# OOBD-Tiger.net
KiCad netlist of a schematic drawn in EAGLE
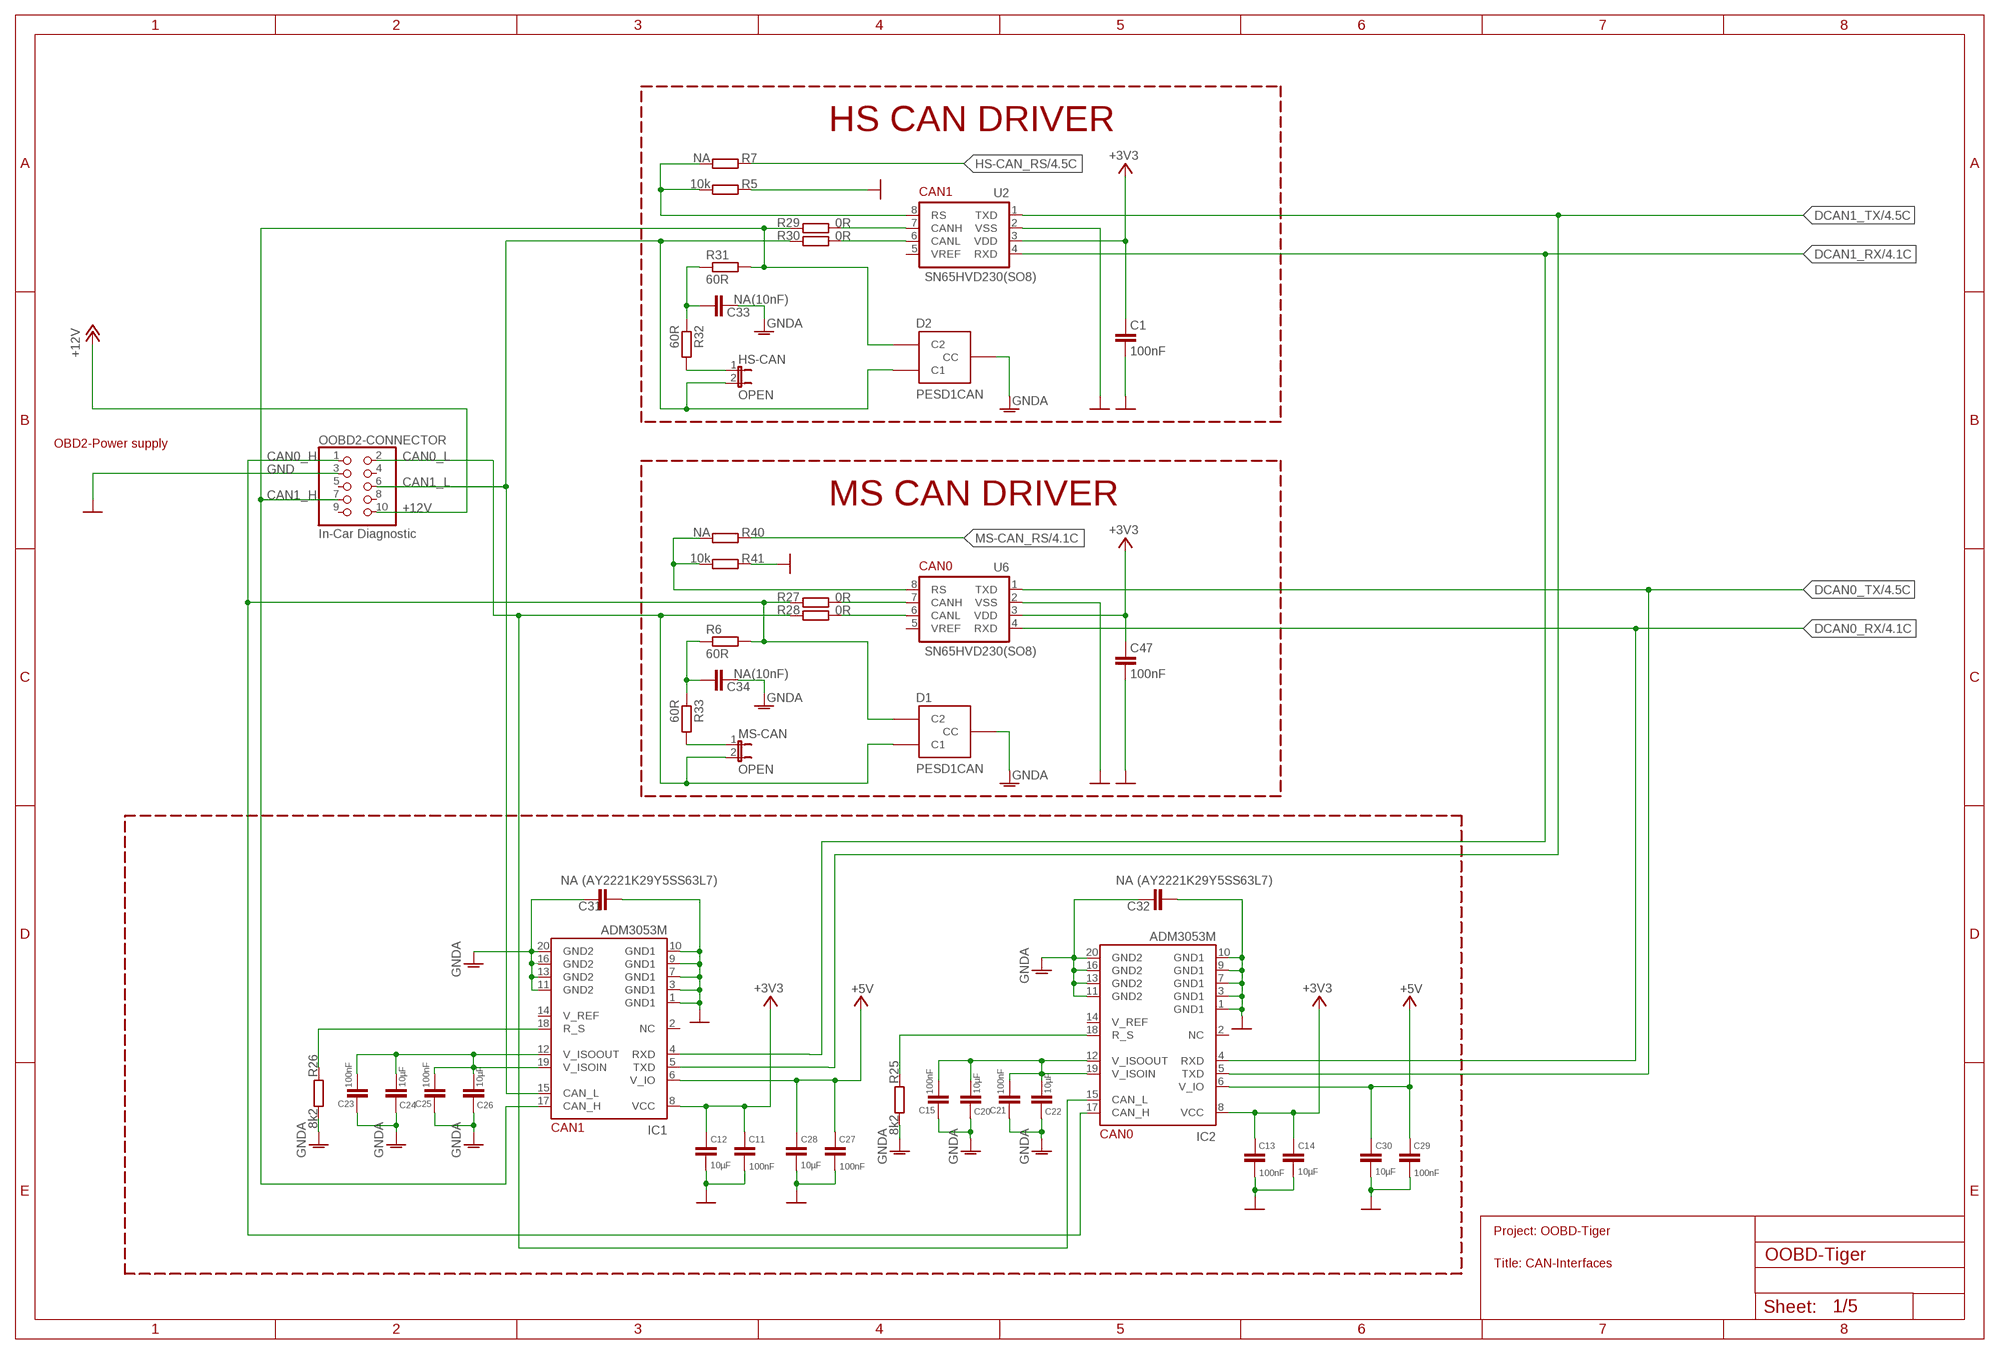
[diagram p0: schematic, sheet 1]
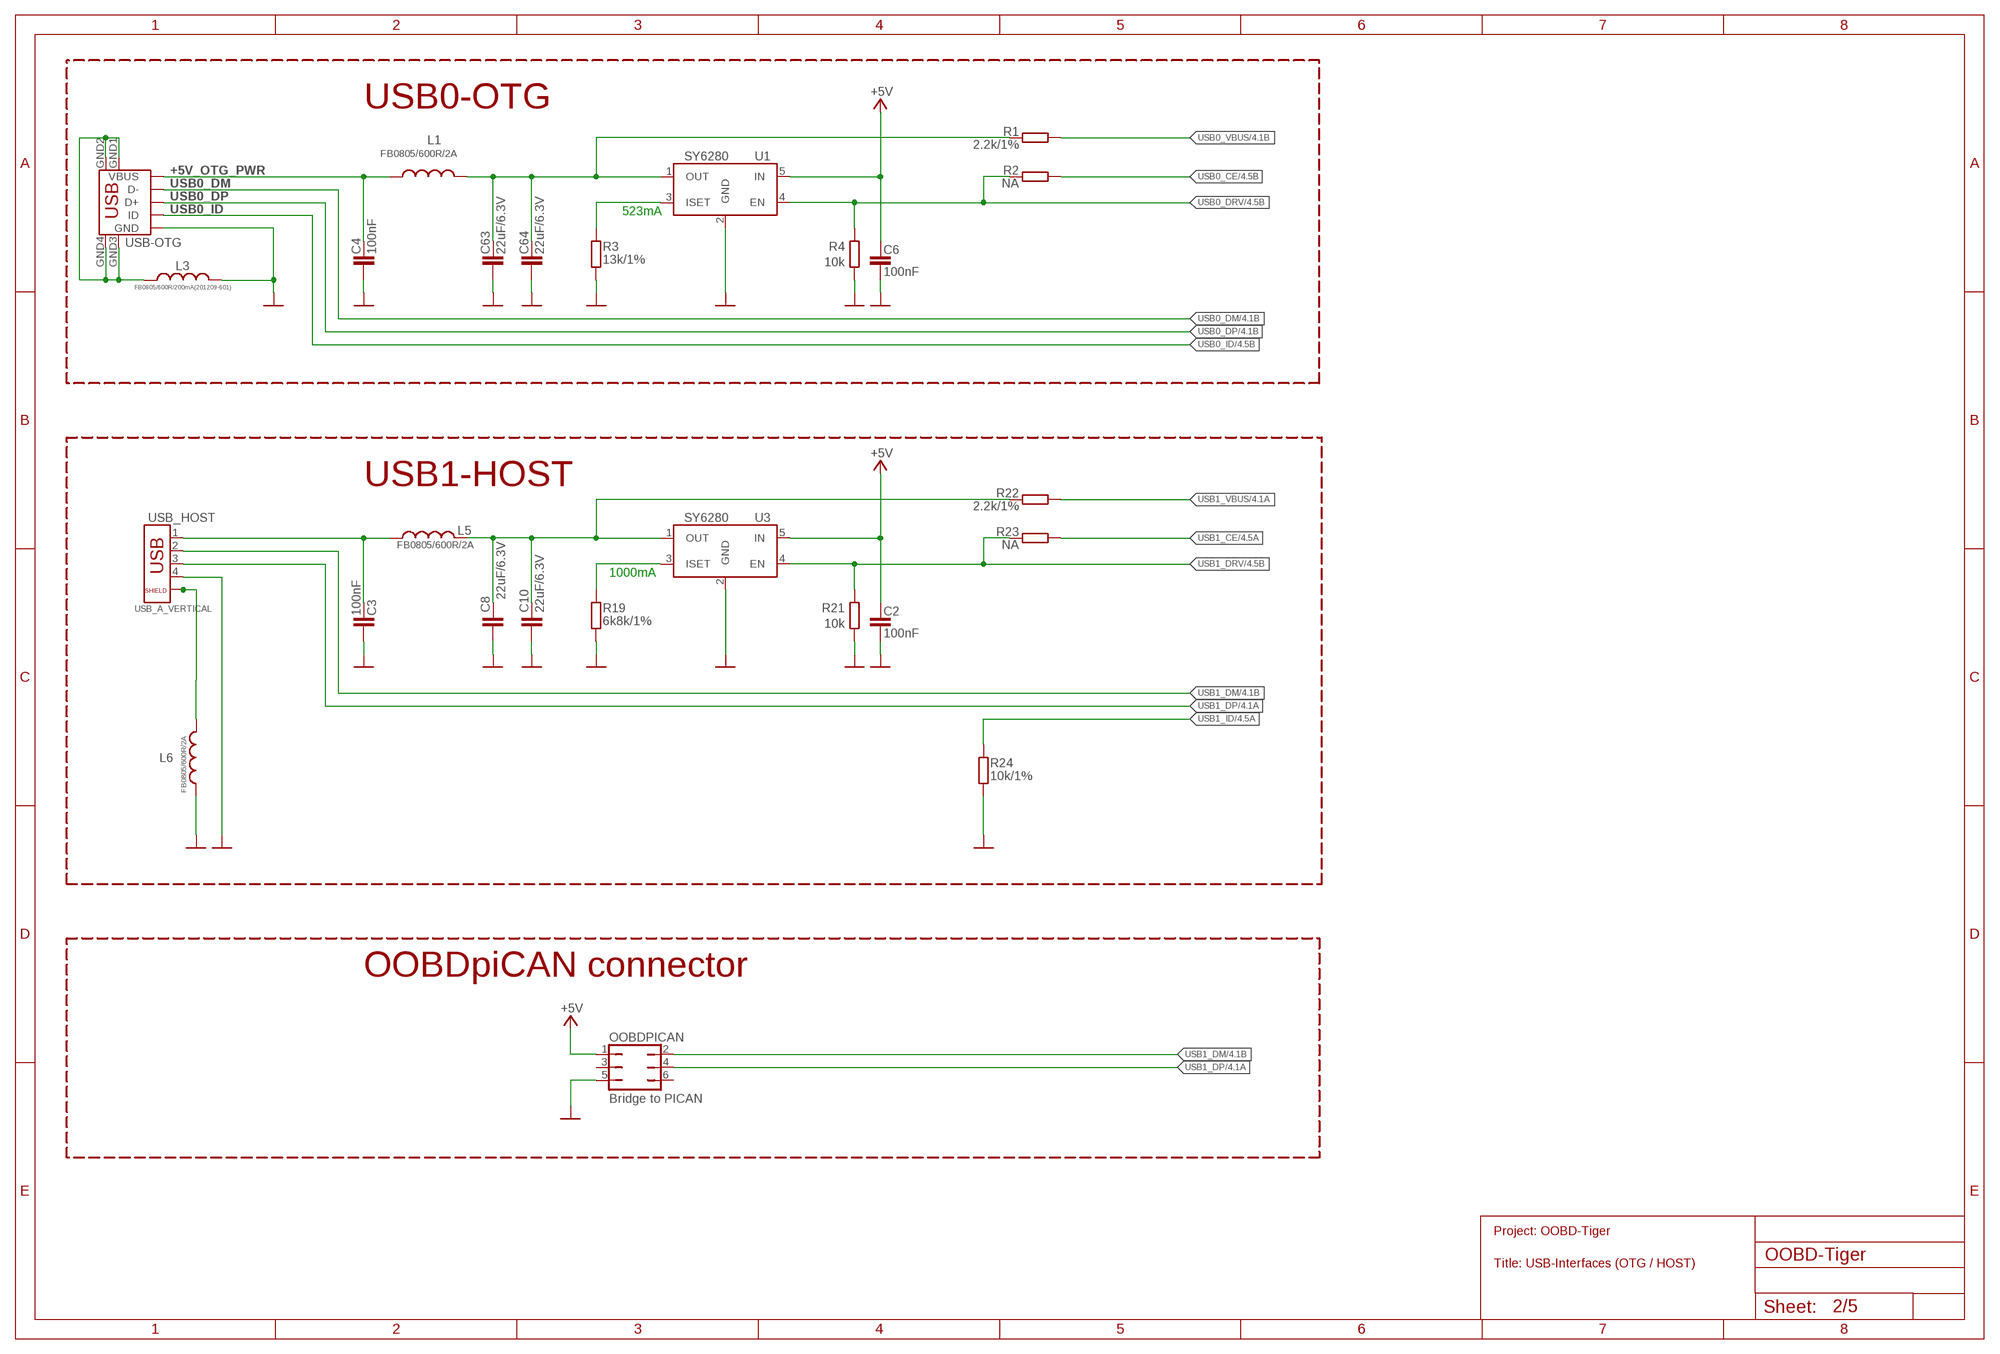
[diagram p1: schematic, sheet 2]
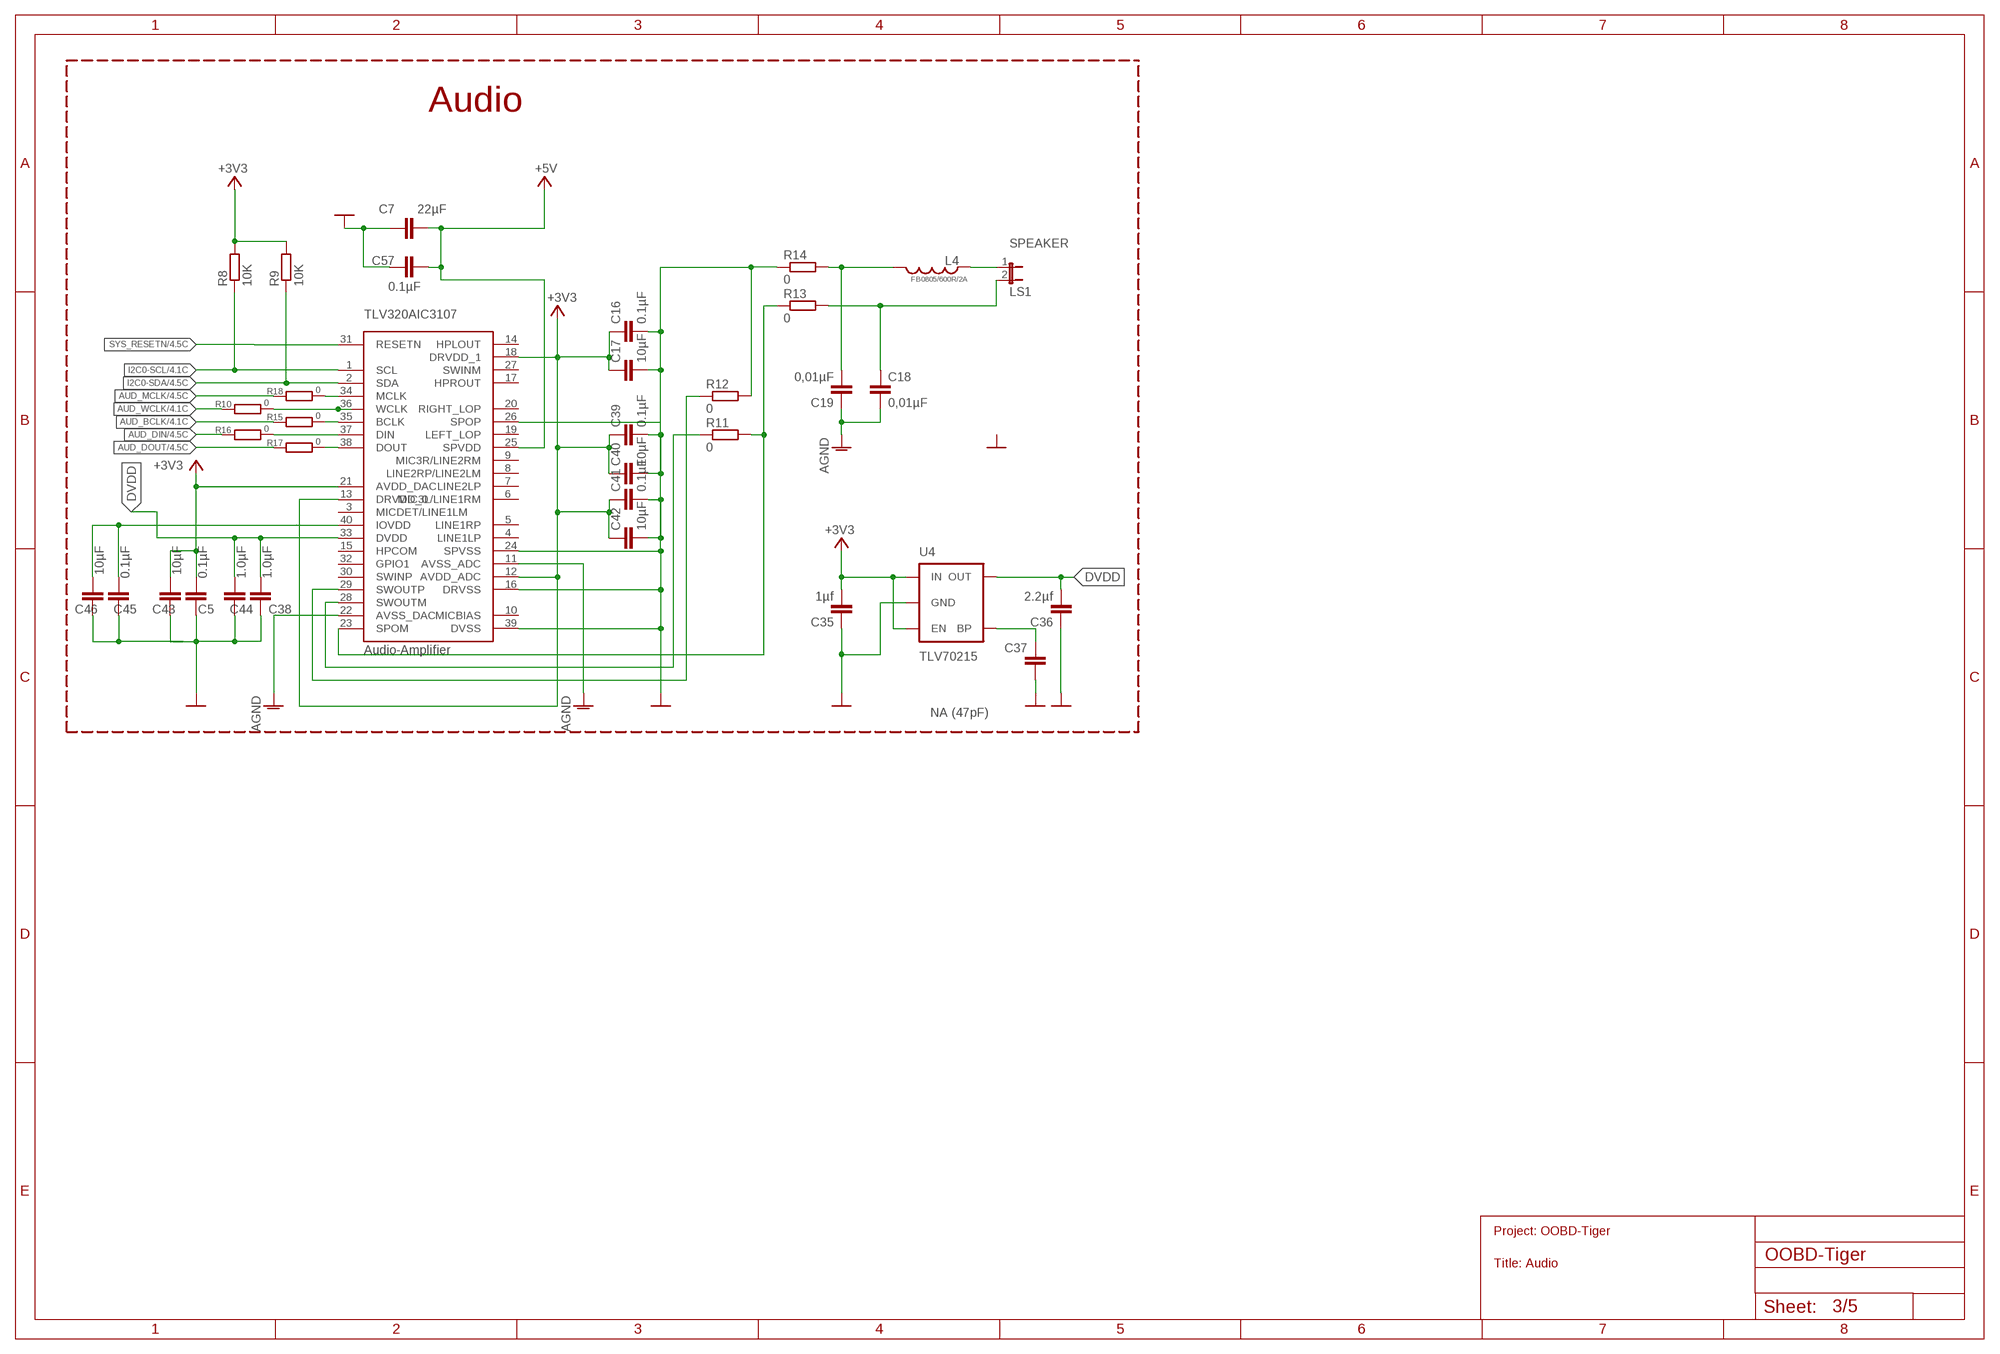
[diagram p2: schematic, sheet 3]
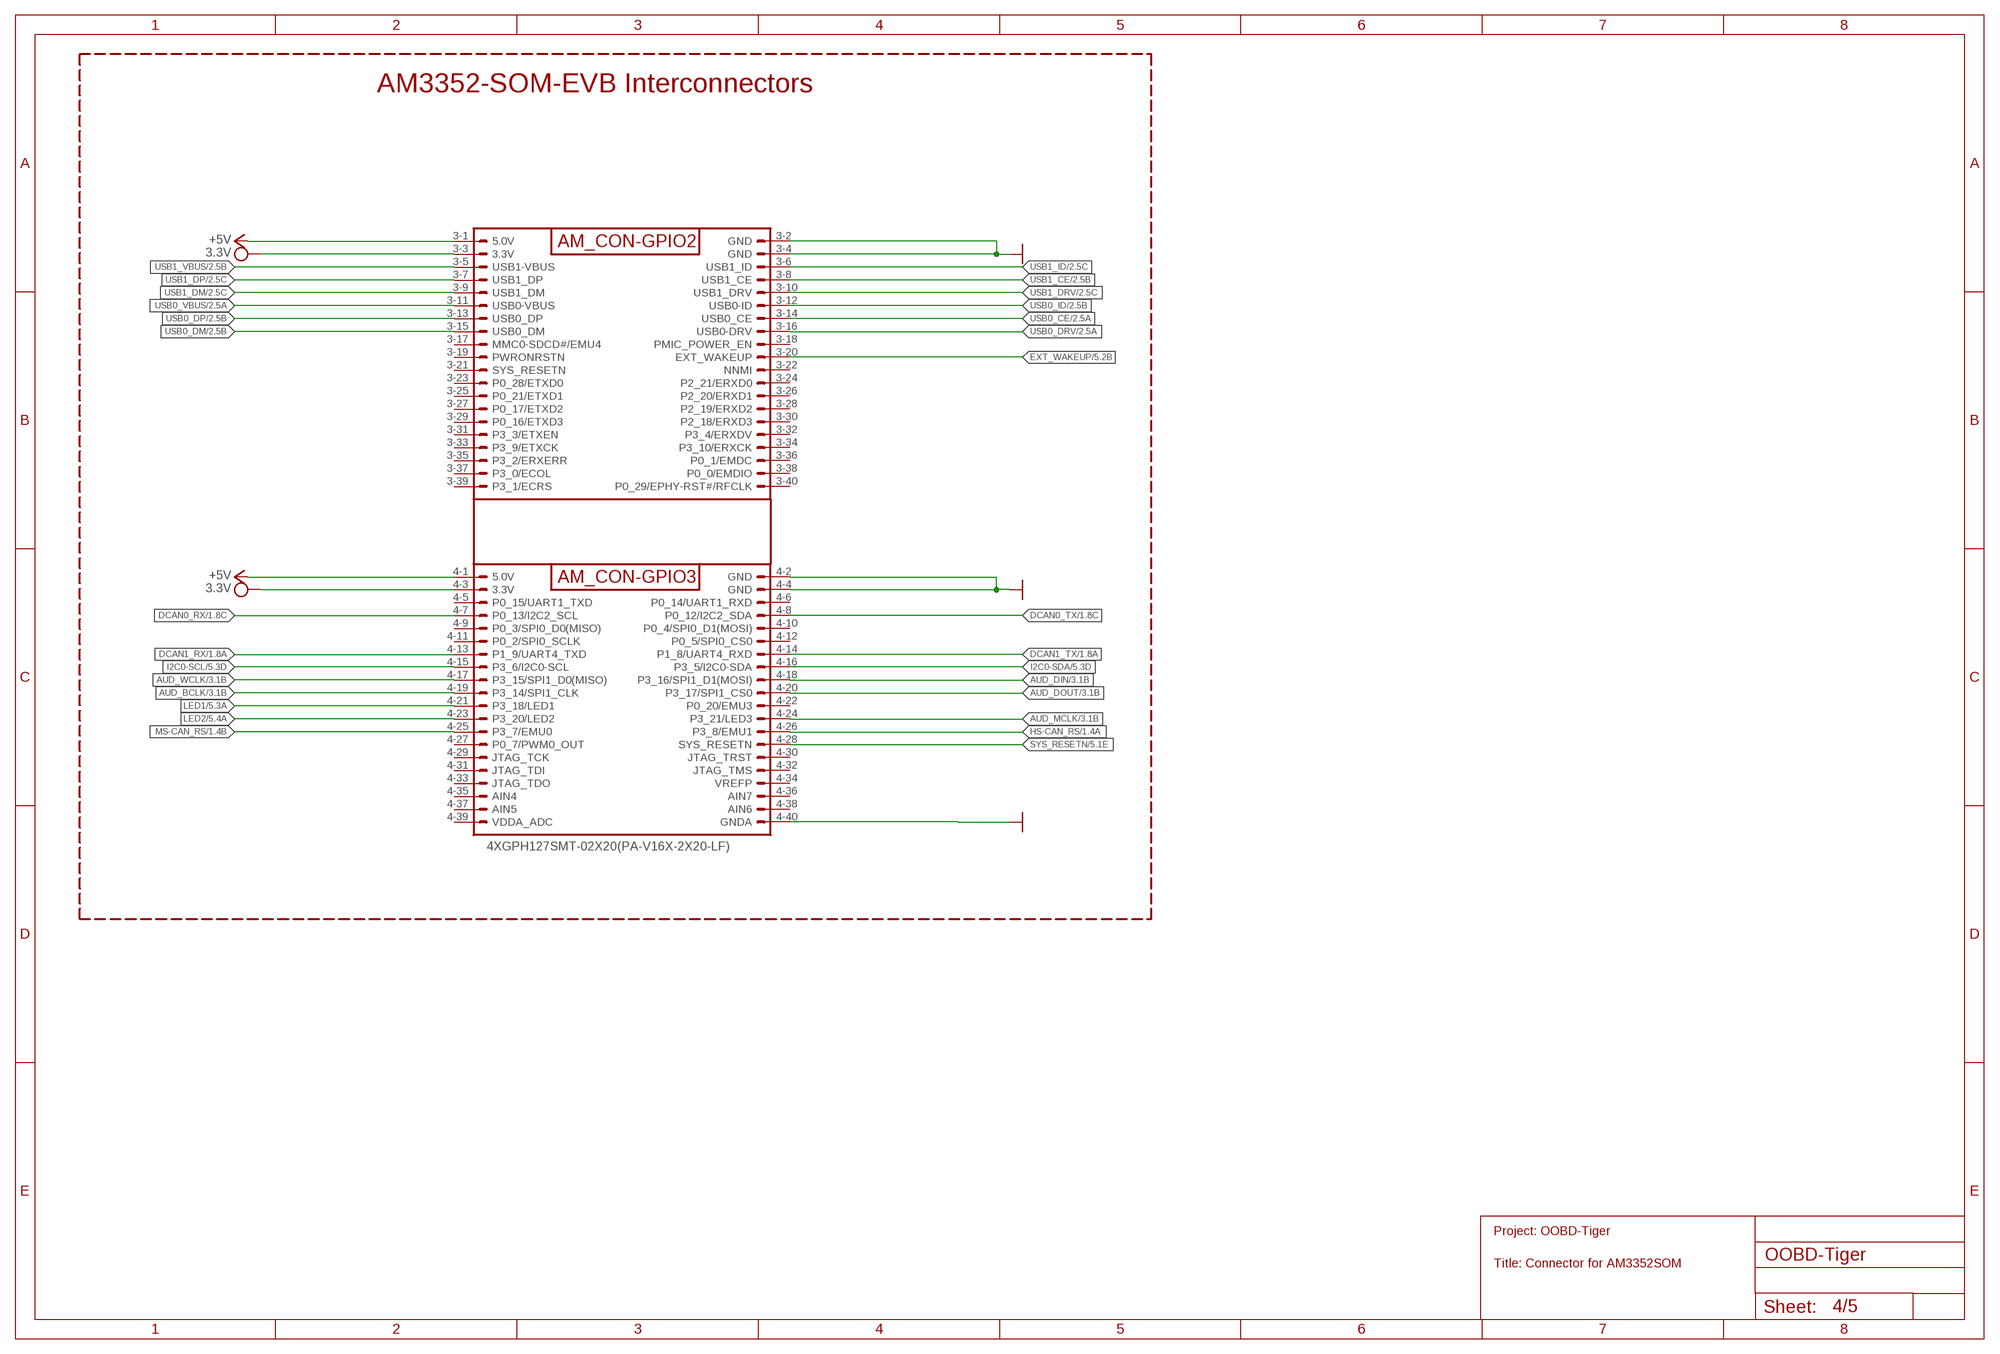
[diagram p3: schematic, sheet 4]
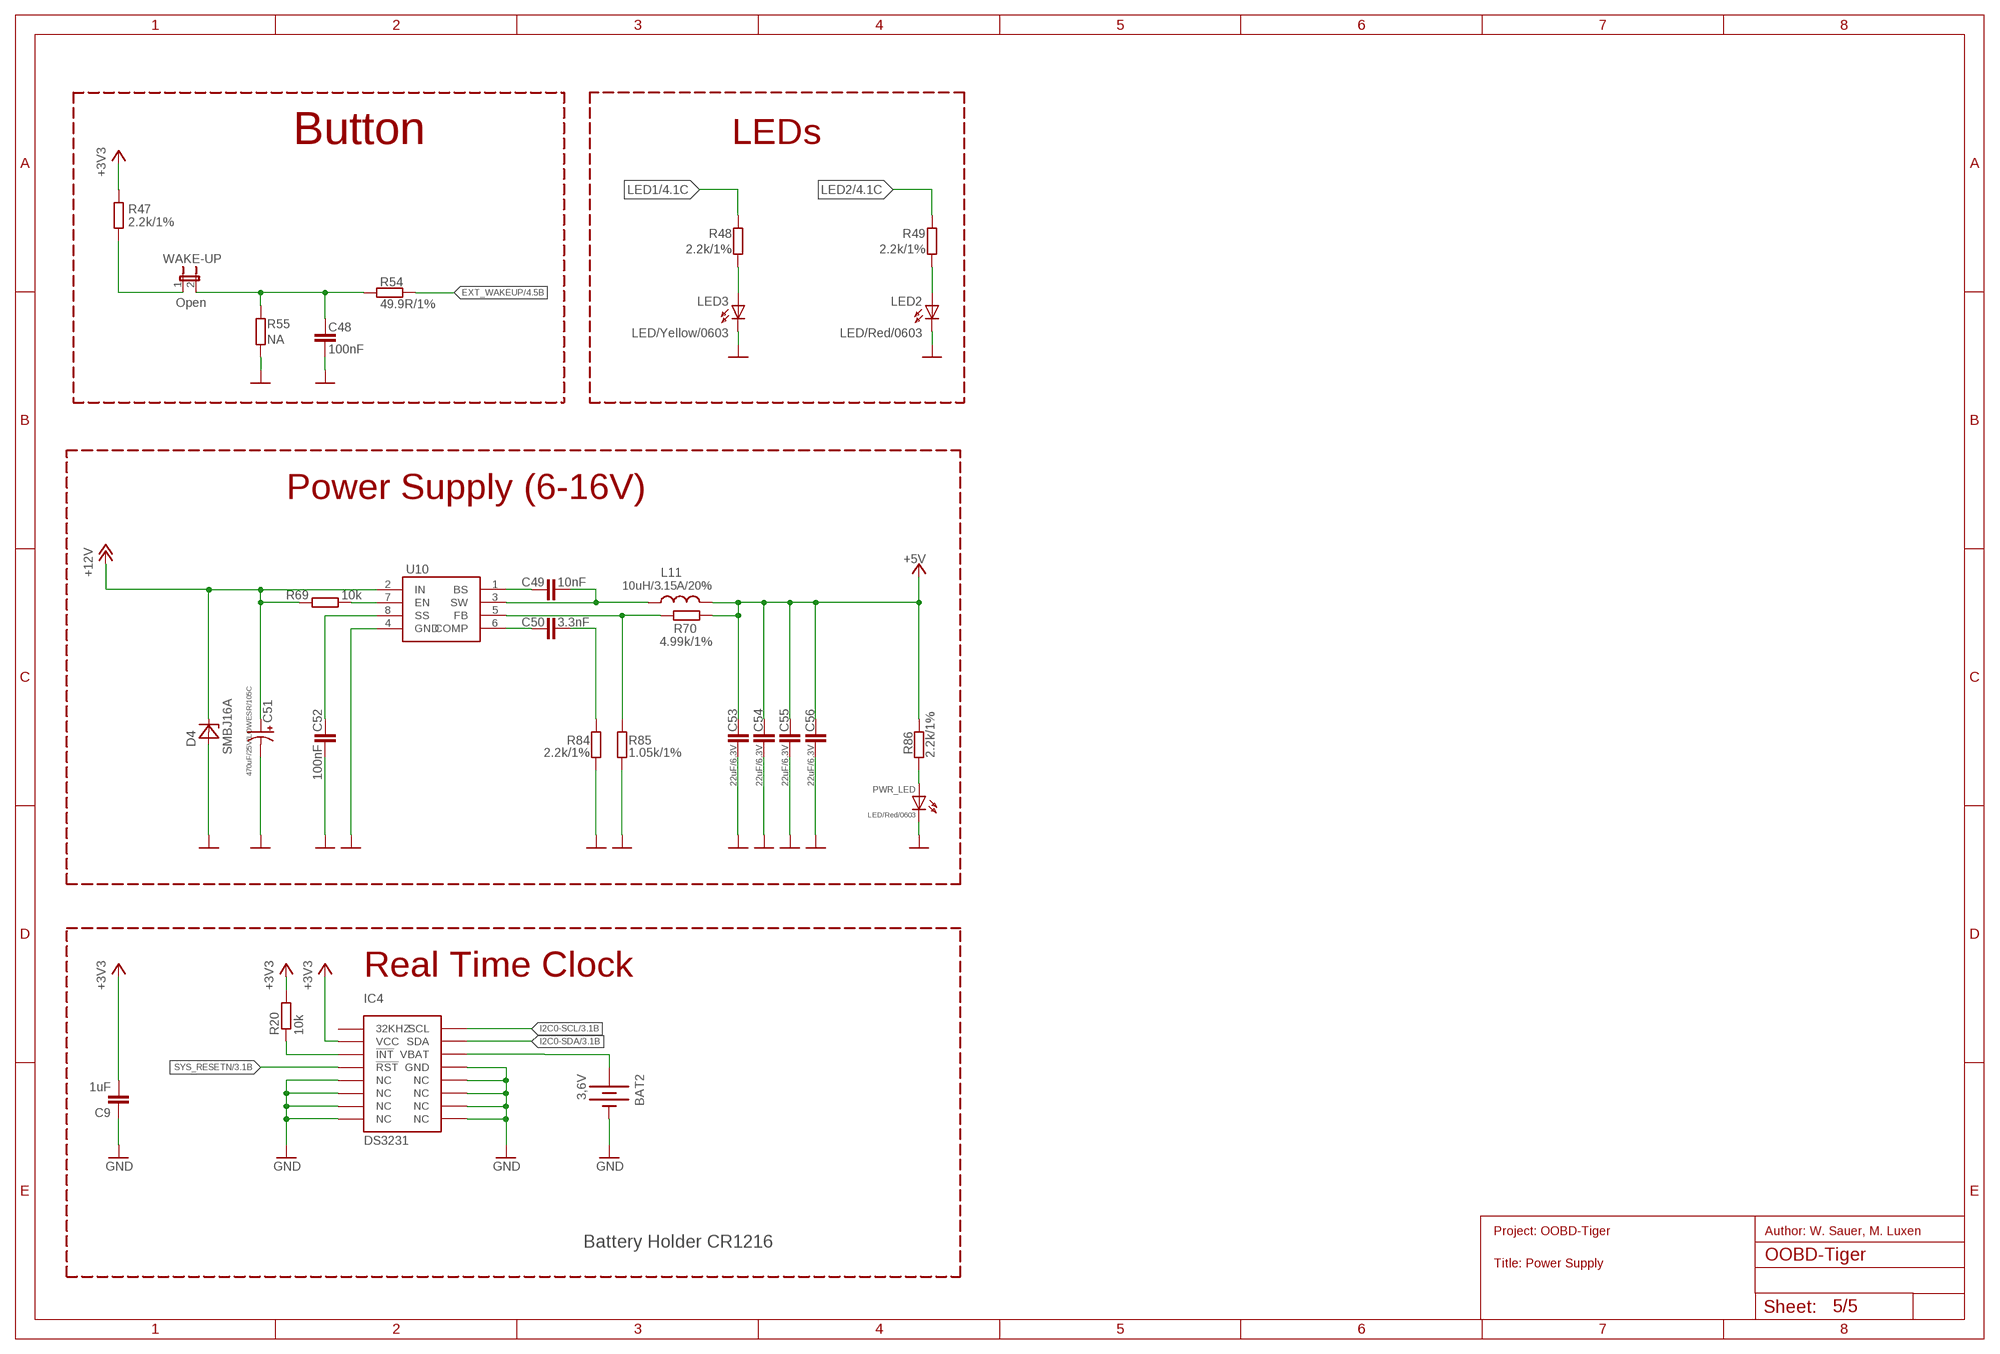
[diagram p4: schematic, sheet 5]

(export (version "E")
  (design (tool "Eeschema 10.0.6"))
  (components
    (comp (ref "C2")
      (value "100nF")
      (footprint "eagle-import:C0603K")
      (libsource (lib "eagle-import") (part "C-EUC0603K"))
    )
    (comp (ref "C3")
      (value "100nF")
      (footprint "eagle-import:C0603K")
      (libsource (lib "eagle-import") (part "C-EUC0603K"))
    )
    (comp (ref "C4")
      (value "100nF")
      (footprint "eagle-import:C0603K")
      (libsource (lib "eagle-import") (part "C-EUC0603K"))
    )
    (comp (ref "C6")
      (value "100nF")
      (footprint "eagle-import:C0603K")
      (libsource (lib "eagle-import") (part "C-EUC0603K"))
    )
    (comp (ref "C8")
      (value "22uF/6.3V")
      (footprint "eagle-import:C0603")
      (libsource (lib "eagle-import") (part "C-EUC0603"))
    )
    (comp (ref "C10")
      (value "22uF/6.3V")
      (footprint "eagle-import:C0603")
      (libsource (lib "eagle-import") (part "C-EUC0603"))
    )
    (comp (ref "C63")
      (value "22uF/6.3V")
      (footprint "eagle-import:C0603")
      (libsource (lib "eagle-import") (part "C-EUC0603"))
    )
    (comp (ref "C64")
      (value "22uF/6.3V")
      (footprint "eagle-import:C0603")
      (libsource (lib "eagle-import") (part "C-EUC0603"))
    )
    (comp (ref "L1")
      (value "FB0805/600R/2A")
      (footprint "eagle-import:L0603")
      (libsource (lib "eagle-import") (part "L-USL0603"))
    )
    (comp (ref "L3")
      (value "FB0805/600R/200mA(201209-601)")
      (footprint "eagle-import:L0603")
      (libsource (lib "eagle-import") (part "L-USL0603"))
    )
    (comp (ref "L5")
      (value "FB0805/600R/2A")
      (footprint "eagle-import:L0603")
      (libsource (lib "eagle-import") (part "L-USL0603"))
    )
    (comp (ref "L6")
      (value "FB0805/600R/2A")
      (footprint "eagle-import:L0603")
      (libsource (lib "eagle-import") (part "L-USL0603"))
    )
    (comp (ref "OOBDPICAN")
      (value "Bridge to PICAN")
      (footprint "eagle-import:JP3Q")
      (libsource (lib "eagle-import") (part "JP3Q"))
    )
    (comp (ref "R1")
      (value "2.2k/1%")
      (footprint "eagle-import:R0603")
      (libsource (lib "eagle-import") (part "R-EU_R0603"))
    )
    (comp (ref "R2")
      (value "NA")
      (footprint "eagle-import:R0603")
      (libsource (lib "eagle-import") (part "R-EU_R0603"))
    )
    (comp (ref "R3")
      (value "13k/1%")
      (footprint "eagle-import:R0603")
      (libsource (lib "eagle-import") (part "R-EU_R0603"))
    )
    (comp (ref "R4")
      (value "10k")
      (footprint "eagle-import:R0603")
      (libsource (lib "eagle-import") (part "R-EU_R0603"))
    )
    (comp (ref "R19")
      (value "6k8k/1%")
      (footprint "eagle-import:R0603")
      (libsource (lib "eagle-import") (part "R-EU_R0603"))
    )
    (comp (ref "R21")
      (value "10k")
      (footprint "eagle-import:R0603")
      (libsource (lib "eagle-import") (part "R-EU_R0603"))
    )
    (comp (ref "R22")
      (value "2.2k/1%")
      (footprint "eagle-import:R0603")
      (libsource (lib "eagle-import") (part "R-EU_R0603"))
    )
    (comp (ref "R23")
      (value "NA")
      (footprint "eagle-import:R0603")
      (libsource (lib "eagle-import") (part "R-EU_R0603"))
    )
    (comp (ref "R24")
      (value "10k/1%")
      (footprint "eagle-import:R0603")
      (libsource (lib "eagle-import") (part "R-EU_R0603"))
    )
    (comp (ref "U1")
      (value "SY6280")
      (footprint "eagle-import:SOT23-5")
      (libsource (lib "eagle-import") (part "SY6280"))
    )
    (comp (ref "U3")
      (value "SY6280")
      (footprint "eagle-import:SOT23-5")
      (libsource (lib "eagle-import") (part "SY6280"))
    )
    (comp (ref "USB_HOST")
      (value "USB_A_VERTICAL")
      (footprint "eagle-import:USB_PN87520_DEV_PTH")
      (libsource (lib "eagle-import") (part "USB_SHIELD1"))
    )
    (comp (ref "USB_OTG")
      (value "USB-OTG")
      (footprint "eagle-import:USB_MINI_9PIN")
      (libsource (lib "eagle-import") (part "MINI_USB9"))
    )
    (comp (ref "C5")
      (value "0.1µF")
      (footprint "eagle-import:0603-CAP")
      (libsource (lib "eagle-import") (part "CAP0603-CAP"))
    )
    (comp (ref "C7")
      (value "22µF")
      (footprint "eagle-import:0603-CAP")
      (libsource (lib "eagle-import") (part "CAP0603-CAP"))
    )
    (comp (ref "C16")
      (value "0.1µF")
      (footprint "eagle-import:0603-CAP")
      (libsource (lib "eagle-import") (part "CAP0603-CAP"))
    )
    (comp (ref "C17")
      (value "10µF")
      (footprint "eagle-import:0603-CAP")
      (libsource (lib "eagle-import") (part "CAP0603-CAP"))
    )
    (comp (ref "C18")
      (value "0,01µF")
      (footprint "eagle-import:0603-CAP")
      (libsource (lib "eagle-import") (part "CAP0603-CAP"))
    )
    (comp (ref "C19")
      (value "0,01µF")
      (footprint "eagle-import:0603-CAP")
      (libsource (lib "eagle-import") (part "CAP0603-CAP"))
    )
    (comp (ref "C35")
      (value "1µf")
      (footprint "eagle-import:0603-CAP")
      (libsource (lib "eagle-import") (part "CAP0603-CAP"))
    )
    (comp (ref "C36")
      (value "2.2µf")
      (footprint "eagle-import:0603-CAP")
      (libsource (lib "eagle-import") (part "CAP0603-CAP"))
    )
    (comp (ref "C37")
      (value "NA (47pF)")
      (footprint "eagle-import:0603-CAP")
      (libsource (lib "eagle-import") (part "CAP0603-CAP"))
    )
    (comp (ref "C38")
      (value "1.0µF")
      (footprint "eagle-import:0603-CAP")
      (libsource (lib "eagle-import") (part "CAP0603-CAP"))
    )
    (comp (ref "C39")
      (value "0.1µF")
      (footprint "eagle-import:0603-CAP")
      (libsource (lib "eagle-import") (part "CAP0603-CAP"))
    )
    (comp (ref "C40")
      (value "10µF")
      (footprint "eagle-import:0603-CAP")
      (libsource (lib "eagle-import") (part "CAP0603-CAP"))
    )
    (comp (ref "C41")
      (value "0.1µF")
      (footprint "eagle-import:0603-CAP")
      (libsource (lib "eagle-import") (part "CAP0603-CAP"))
    )
    (comp (ref "C42")
      (value "10µF")
      (footprint "eagle-import:0603-CAP")
      (libsource (lib "eagle-import") (part "CAP0603-CAP"))
    )
    (comp (ref "C43")
      (value "10µF")
      (footprint "eagle-import:0603-CAP")
      (libsource (lib "eagle-import") (part "CAP0603-CAP"))
    )
    (comp (ref "C44")
      (value "1.0µF")
      (footprint "eagle-import:0603-CAP")
      (libsource (lib "eagle-import") (part "CAP0603-CAP"))
    )
    (comp (ref "C45")
      (value "0.1µF")
      (footprint "eagle-import:0603-CAP")
      (libsource (lib "eagle-import") (part "CAP0603-CAP"))
    )
    (comp (ref "C46")
      (value "10µF")
      (footprint "eagle-import:0603-CAP")
      (libsource (lib "eagle-import") (part "CAP0603-CAP"))
    )
    (comp (ref "C57")
      (value "0.1µF")
      (footprint "eagle-import:0603-CAP")
      (libsource (lib "eagle-import") (part "CAP0603-CAP"))
    )
    (comp (ref "L4")
      (value "FB0805/600R/2A")
      (footprint "eagle-import:L0603")
      (libsource (lib "eagle-import") (part "L-USL0603"))
    )
    (comp (ref "R8")
      (value "10K")
      (footprint "eagle-import:R0603")
      (libsource (lib "eagle-import") (part "resistor_R-EU_R0603"))
    )
    (comp (ref "R9")
      (value "10K")
      (footprint "eagle-import:R0603")
      (libsource (lib "eagle-import") (part "resistor_R-EU_R0603"))
    )
    (comp (ref "R10")
      (value "0")
      (footprint "eagle-import:R0603")
      (libsource (lib "eagle-import") (part "resistor_R-EU_R0603"))
    )
    (comp (ref "R11")
      (value "0")
      (footprint "eagle-import:R0603")
      (libsource (lib "eagle-import") (part "resistor_R-EU_R0603"))
    )
    (comp (ref "R12")
      (value "0")
      (footprint "eagle-import:R0603")
      (libsource (lib "eagle-import") (part "resistor_R-EU_R0603"))
    )
    (comp (ref "R13")
      (value "0")
      (footprint "eagle-import:R0603")
      (libsource (lib "eagle-import") (part "resistor_R-EU_R0603"))
    )
    (comp (ref "R14")
      (value "0")
      (footprint "eagle-import:R0603")
      (libsource (lib "eagle-import") (part "resistor_R-EU_R0603"))
    )
    (comp (ref "R15")
      (value "0")
      (footprint "eagle-import:R0603")
      (libsource (lib "eagle-import") (part "resistor_R-EU_R0603"))
    )
    (comp (ref "R16")
      (value "0")
      (footprint "eagle-import:R0603")
      (libsource (lib "eagle-import") (part "resistor_R-EU_R0603"))
    )
    (comp (ref "R17")
      (value "0")
      (footprint "eagle-import:R0603")
      (libsource (lib "eagle-import") (part "resistor_R-EU_R0603"))
    )
    (comp (ref "R18")
      (value "0")
      (footprint "eagle-import:R0603")
      (libsource (lib "eagle-import") (part "resistor_R-EU_R0603"))
    )
    (comp (ref "SPEAKER")
      (value "LS1")
      (footprint "eagle-import:1X02")
      (libsource (lib "eagle-import") (part "JUMPER-2PTH"))
    )
    (comp (ref "TLV320AIC3107")
      (value "Audio-Amplifier")
      (footprint "eagle-import:QFN40-6X6")
      (libsource (lib "eagle-import") (part "TLV320AIC3107"))
    )
    (comp (ref "U4")
      (value "TLV70215")
      (footprint "eagle-import:SOT23-5")
      (libsource (lib "eagle-import") (part "V_REG_LDOSMD"))
    )
    (comp (ref "C1")
      (value "100nF")
      (footprint "eagle-import:C0603K")
      (libsource (lib "eagle-import") (part "C-EUC0603K"))
    )
    (comp (ref "C11")
      (value "100nF")
      (footprint "eagle-import:C0603K")
      (libsource (lib "eagle-import") (part "C-EUC0603K"))
    )
    (comp (ref "C12")
      (value "10µF")
      (footprint "eagle-import:C0805K")
      (libsource (lib "eagle-import") (part "C-EUC0805K"))
    )
    (comp (ref "C13")
      (value "100nF")
      (footprint "eagle-import:C0603K")
      (libsource (lib "eagle-import") (part "C-EUC0603K"))
    )
    (comp (ref "C14")
      (value "10µF")
      (footprint "eagle-import:C0805K")
      (libsource (lib "eagle-import") (part "C-EUC0805K"))
    )
    (comp (ref "C15")
      (value "100nF")
      (footprint "eagle-import:C0603K")
      (libsource (lib "eagle-import") (part "C-EUC0603K"))
    )
    (comp (ref "C20")
      (value "10µF")
      (footprint "eagle-import:C0805K")
      (libsource (lib "eagle-import") (part "C-EUC0805K"))
    )
    (comp (ref "C21")
      (value "100nF")
      (footprint "eagle-import:C0603K")
      (libsource (lib "eagle-import") (part "C-EUC0603K"))
    )
    (comp (ref "C22")
      (value "10µF")
      (footprint "eagle-import:C0805K")
      (libsource (lib "eagle-import") (part "C-EUC0805K"))
    )
    (comp (ref "C23")
      (value "100nF")
      (footprint "eagle-import:C0603K")
      (libsource (lib "eagle-import") (part "C-EUC0603K"))
    )
    (comp (ref "C24")
      (value "10µF")
      (footprint "eagle-import:C0805K")
      (libsource (lib "eagle-import") (part "C-EUC0805K"))
    )
    (comp (ref "C25")
      (value "100nF")
      (footprint "eagle-import:C0603K")
      (libsource (lib "eagle-import") (part "C-EUC0603K"))
    )
    (comp (ref "C26")
      (value "10µF")
      (footprint "eagle-import:C0805K")
      (libsource (lib "eagle-import") (part "C-EUC0805K"))
    )
    (comp (ref "C27")
      (value "100nF")
      (footprint "eagle-import:C0603K")
      (libsource (lib "eagle-import") (part "C-EUC0603K"))
    )
    (comp (ref "C28")
      (value "10µF")
      (footprint "eagle-import:C0805K")
      (libsource (lib "eagle-import") (part "C-EUC0805K"))
    )
    (comp (ref "C29")
      (value "100nF")
      (footprint "eagle-import:C0603K")
      (libsource (lib "eagle-import") (part "C-EUC0603K"))
    )
    (comp (ref "C30")
      (value "10µF")
      (footprint "eagle-import:C0805K")
      (libsource (lib "eagle-import") (part "C-EUC0805K"))
    )
    (comp (ref "C31")
      (value "NA (AY2221K29Y5SS63L7)")
      (footprint "eagle-import:C075-032X103")
      (libsource (lib "eagle-import") (part "C-EU075-032X103"))
    )
    (comp (ref "C32")
      (value "NA (AY2221K29Y5SS63L7)")
      (footprint "eagle-import:C075-032X103")
      (libsource (lib "eagle-import") (part "C-EU075-032X103"))
    )
    (comp (ref "C33")
      (value "NA(10nF)")
      (footprint "eagle-import:C0603")
      (libsource (lib "eagle-import") (part "resistor_C-EUC0603"))
    )
    (comp (ref "C34")
      (value "NA(10nF)")
      (footprint "eagle-import:C0603")
      (libsource (lib "eagle-import") (part "resistor_C-EUC0603"))
    )
    (comp (ref "C47")
      (value "100nF")
      (footprint "eagle-import:C0603K")
      (libsource (lib "eagle-import") (part "C-EUC0603K"))
    )
    (comp (ref "D1")
      (value "PESD1CAN")
      (footprint "eagle-import:SOT23")
      (libsource (lib "eagle-import") (part "PESD1CAN"))
    )
    (comp (ref "D2")
      (value "PESD1CAN")
      (footprint "eagle-import:SOT23")
      (libsource (lib "eagle-import") (part "PESD1CAN"))
    )
    (comp (ref "HS-CAN")
      (value "OPEN")
      (footprint "eagle-import:1X02")
      (libsource (lib "eagle-import") (part "JUMPER-2PTH"))
    )
    (comp (ref "IC1")
      (value "ADM3053M")
      (footprint "eagle-import:SO20W")
      (libsource (lib "eagle-import") (part "ADM3053M"))
    )
    (comp (ref "IC2")
      (value "ADM3053M")
      (footprint "eagle-import:SO20W")
      (libsource (lib "eagle-import") (part "ADM3053M"))
    )
    (comp (ref "MS-CAN")
      (value "OPEN")
      (footprint "eagle-import:1X02")
      (libsource (lib "eagle-import") (part "JUMPER-2PTH"))
    )
    (comp (ref "OOBD2-CONNECTOR")
      (value "In-Car Diagnostic")
      (footprint "eagle-import:2X05_90")
      (libsource (lib "eagle-import") (part "PINHD-2X5/90"))
    )
    (comp (ref "R5")
      (value "10k")
      (footprint "eagle-import:R0603")
      (libsource (lib "eagle-import") (part "R-EU_R0603"))
    )
    (comp (ref "R6")
      (value "60R")
      (footprint "eagle-import:R0603")
      (libsource (lib "eagle-import") (part "resistor_R-EU_R0603"))
    )
    (comp (ref "R7")
      (value "NA")
      (footprint "eagle-import:R0603")
      (libsource (lib "eagle-import") (part "R-EU_R0603"))
    )
    (comp (ref "R25")
      (value "8k2")
      (footprint "eagle-import:R0603")
      (libsource (lib "eagle-import") (part "R-EU_R0603"))
    )
    (comp (ref "R26")
      (value "8k2")
      (footprint "eagle-import:R0603")
      (libsource (lib "eagle-import") (part "R-EU_R0603"))
    )
    (comp (ref "R27")
      (value "0R")
      (footprint "eagle-import:0207_10")
      (libsource (lib "eagle-import") (part "R-EU_0207/10"))
    )
    (comp (ref "R28")
      (value "0R")
      (footprint "eagle-import:0207_10")
      (libsource (lib "eagle-import") (part "R-EU_0207/10"))
    )
    (comp (ref "R29")
      (value "0R")
      (footprint "eagle-import:0207_10")
      (libsource (lib "eagle-import") (part "R-EU_0207/10"))
    )
    (comp (ref "R30")
      (value "0R")
      (footprint "eagle-import:0207_10")
      (libsource (lib "eagle-import") (part "R-EU_0207/10"))
    )
    (comp (ref "R31")
      (value "60R")
      (footprint "eagle-import:R0603")
      (libsource (lib "eagle-import") (part "resistor_R-EU_R0603"))
    )
    (comp (ref "R32")
      (value "60R")
      (footprint "eagle-import:R0603")
      (libsource (lib "eagle-import") (part "resistor_R-EU_R0603"))
    )
    (comp (ref "R33")
      (value "60R")
      (footprint "eagle-import:R0603")
      (libsource (lib "eagle-import") (part "resistor_R-EU_R0603"))
    )
    (comp (ref "R40")
      (value "NA")
      (footprint "eagle-import:R0603")
      (libsource (lib "eagle-import") (part "R-EU_R0603"))
    )
    (comp (ref "R41")
      (value "10k")
      (footprint "eagle-import:R0603")
      (libsource (lib "eagle-import") (part "R-EU_R0603"))
    )
    (comp (ref "U2")
      (value "SN65HVD230(SO8)")
      (footprint "eagle-import:SO-08")
      (libsource (lib "eagle-import") (part "MCP2551"))
    )
    (comp (ref "U6")
      (value "SN65HVD230(SO8)")
      (footprint "eagle-import:SO-08")
      (libsource (lib "eagle-import") (part "MCP2551"))
    )
    (comp (ref "AM3352-SOM-EVB-PLATFORM")
      (value "4XGPH127SMT-02X20(PA-V16X-2X20-LF)")
      (footprint "eagle-import:OOBD-TIGER-AM3352-SOM")
      (libsource (lib "eagle-import") (part "OOBD-TIGER-AM3352-SOM---4XGPH127SMT-02X20(PA-V16X-2X20-LF)"))
    )
    (comp (ref "BAT2")
      (value "3,6V")
      (footprint "eagle-import:BATTCON_12MM_PTH")
      (libsource (lib "eagle-import") (part "BATTERY12PTH"))
    )
    (comp (ref "C9")
      (value "1uF")
      (footprint "eagle-import:C0603")
      (libsource (lib "eagle-import") (part "C-EUC0603"))
    )
    (comp (ref "C48")
      (value "100nF")
      (footprint "eagle-import:C0603")
      (libsource (lib "eagle-import") (part "C-EUC0603"))
    )
    (comp (ref "C49")
      (value "10nF")
      (footprint "eagle-import:C0603")
      (libsource (lib "eagle-import") (part "C-EUC0603"))
    )
    (comp (ref "C50")
      (value "3.3nF")
      (footprint "eagle-import:C0603")
      (libsource (lib "eagle-import") (part "C-EUC0603"))
    )
    (comp (ref "C51")
      (value "470uF/25V/LOWESR/105C")
      (footprint "eagle-import:PANASONIC_D")
      (libsource (lib "eagle-import") (part "47UF-50V-20%(ELECT)"))
    )
    (comp (ref "C52")
      (value "100nF")
      (footprint "eagle-import:C0603")
      (libsource (lib "eagle-import") (part "C-EUC0603"))
    )
    (comp (ref "C53")
      (value "22uF/6.3V")
      (footprint "eagle-import:C0603")
      (libsource (lib "eagle-import") (part "C-EUC0603"))
    )
    (comp (ref "C54")
      (value "22uF/6.3V")
      (footprint "eagle-import:C0603")
      (libsource (lib "eagle-import") (part "C-EUC0603"))
    )
    (comp (ref "C55")
      (value "22uF/6.3V")
      (footprint "eagle-import:C0603")
      (libsource (lib "eagle-import") (part "C-EUC0603"))
    )
    (comp (ref "C56")
      (value "22uF/6.3V")
      (footprint "eagle-import:C0603")
      (libsource (lib "eagle-import") (part "C-EUC0603"))
    )
    (comp (ref "D4")
      (value "SMBJ16A")
      (footprint "eagle-import:DO214AA")
      (libsource (lib "eagle-import") (part "SMBJ16A"))
    )
    (comp (ref "IC4")
      (value "DS3231")
      (footprint "eagle-import:SOIC-16W")
      (libsource (lib "eagle-import") (part "DS3231SOIC-16W"))
    )
    (comp (ref "L11")
      (value "10uH/3.15A/20%")
      (footprint "eagle-import:8X8MM_3131")
      (libsource (lib "eagle-import") (part "LLQH88PN100M38"))
    )
    (comp (ref "LED2")
      (value "LED/Red/0603")
      (footprint "eagle-import:LED_0603")
      (libsource (lib "eagle-import") (part "LEDLED_0603"))
    )
    (comp (ref "LED3")
      (value "LED/Yellow/0603")
      (footprint "eagle-import:LED_0603")
      (libsource (lib "eagle-import") (part "LEDLED_0603"))
    )
    (comp (ref "PWR_LED")
      (value "LED/Red/0603")
      (footprint "eagle-import:LED-0603")
      (libsource (lib "eagle-import") (part "LED0603DWS"))
    )
    (comp (ref "R20")
      (value "10k")
      (footprint "eagle-import:R0603")
      (libsource (lib "eagle-import") (part "R-EU_R0603"))
    )
    (comp (ref "R47")
      (value "2.2k/1%")
      (footprint "eagle-import:R0603")
      (libsource (lib "eagle-import") (part "R-EU_R0603"))
    )
    (comp (ref "R48")
      (value "2.2k/1%")
      (footprint "eagle-import:R0603")
      (libsource (lib "eagle-import") (part "R-EU_R0603"))
    )
    (comp (ref "R49")
      (value "2.2k/1%")
      (footprint "eagle-import:R0603")
      (libsource (lib "eagle-import") (part "R-EU_R0603"))
    )
    (comp (ref "R54")
      (value "49.9R/1%")
      (footprint "eagle-import:R0603")
      (libsource (lib "eagle-import") (part "R-EU_R0603"))
    )
    (comp (ref "R55")
      (value "NA")
      (footprint "eagle-import:R0603")
      (libsource (lib "eagle-import") (part "R-EU_R0603"))
    )
    (comp (ref "R69")
      (value "10k")
      (footprint "eagle-import:R0603")
      (libsource (lib "eagle-import") (part "R-EU_R0603"))
    )
    (comp (ref "R70")
      (value "4.99k/1%")
      (footprint "eagle-import:R0603")
      (libsource (lib "eagle-import") (part "R-EU_R0603"))
    )
    (comp (ref "R84")
      (value "2.2k/1%")
      (footprint "eagle-import:R0603")
      (libsource (lib "eagle-import") (part "R-EU_R0603"))
    )
    (comp (ref "R85")
      (value "1.05k/1%")
      (footprint "eagle-import:R0603")
      (libsource (lib "eagle-import") (part "R-EU_R0603"))
    )
    (comp (ref "R86")
      (value "2.2k/1%")
      (footprint "eagle-import:R0603")
      (libsource (lib "eagle-import") (part "R-EU_R0603"))
    )
    (comp (ref "U10")
      (value "MP1482DS")
      (footprint "eagle-import:SOIC8")
      (libsource (lib "eagle-import") (part "MP1482"))
    )
    (comp (ref "WAKE-UP")
      (value "Open")
      (footprint "eagle-import:1X02_LOCK")
      (libsource (lib "eagle-import") (part "JUMPER-2PTH_LOCK"))
    )
  )
  (nets
    (net (code "1") (name "+3V3") (class "Default")
      (node (ref "C1") (pin "1") (pinfunction "1_1") (pintype "passive"))
      (node (ref "C11") (pin "1") (pinfunction "1_1") (pintype "passive"))
      (node (ref "C12") (pin "1") (pinfunction "1_1") (pintype "passive"))
      (node (ref "C13") (pin "1") (pinfunction "1_1") (pintype "passive"))
      (node (ref "C14") (pin "1") (pinfunction "1_1") (pintype "passive"))
      (node (ref "C16") (pin "1") (pinfunction "1_1") (pintype "passive"))
      (node (ref "C17") (pin "1") (pinfunction "1_1") (pintype "passive"))
      (node (ref "C35") (pin "2") (pinfunction "2_2") (pintype "passive"))
      (node (ref "C39") (pin "1") (pinfunction "1_1") (pintype "passive"))
      (node (ref "C40") (pin "1") (pinfunction "1_1") (pintype "passive"))
      (node (ref "C41") (pin "1") (pinfunction "1_1") (pintype "passive"))
      (node (ref "C42") (pin "1") (pinfunction "1_1") (pintype "passive"))
      (node (ref "C43") (pin "2") (pinfunction "2_2") (pintype "passive"))
      (node (ref "C47") (pin "1") (pinfunction "1_1") (pintype "passive"))
      (node (ref "C5") (pin "2") (pinfunction "2_2") (pintype "passive"))
      (node (ref "C9") (pin "2") (pinfunction "2_2") (pintype "passive"))
      (node (ref "IC1") (pin "8") (pinfunction "VCC_8") (pintype "power_in"))
      (node (ref "IC2") (pin "8") (pinfunction "VCC_8") (pintype "power_in"))
      (node (ref "IC4") (pin "2") (pinfunction "VCC_2") (pintype "bidirectional"))
      (node (ref "R20") (pin "2") (pinfunction "2_2") (pintype "passive"))
      (node (ref "R47") (pin "2") (pinfunction "2_2") (pintype "passive"))
      (node (ref "R8") (pin "2") (pinfunction "2_2") (pintype "passive"))
      (node (ref "R9") (pin "2") (pinfunction "2_2") (pintype "passive"))
      (node (ref "TLV320AIC3107") (pin "12") (pinfunction "AVDD_ADC_12") (pintype "bidirectional"))
      (node (ref "TLV320AIC3107") (pin "13") (pinfunction "DRVDD_0_13") (pintype "bidirectional"))
      (node (ref "TLV320AIC3107") (pin "18") (pinfunction "DRVDD_1_18") (pintype "bidirectional"))
      (node (ref "TLV320AIC3107") (pin "21") (pinfunction "AVDD_DAC_21") (pintype "bidirectional"))
      (node (ref "U2") (pin "3") (pinfunction "VDD_3") (pintype "power_in"))
      (node (ref "U4") (pin "1") (pinfunction "IN_1") (pintype "input"))
      (node (ref "U4") (pin "3") (pinfunction "EN_3") (pintype "input"))
      (node (ref "U6") (pin "3") (pinfunction "VDD_3") (pintype "power_in"))
    )
    (net (code "2") (name "+5V") (class "Default")
      (node (ref "AM3352-SOM-EVB-PLATFORM") (pin "3-1") (pinfunction "5.0V_3-1") (pintype "passive"))
      (node (ref "AM3352-SOM-EVB-PLATFORM") (pin "4-1") (pinfunction "5.0V_4-1") (pintype "passive"))
      (node (ref "C2") (pin "1") (pinfunction "1_1") (pintype "passive"))
      (node (ref "C27") (pin "1") (pinfunction "1_1") (pintype "passive"))
      (node (ref "C28") (pin "1") (pinfunction "1_1") (pintype "passive"))
      (node (ref "C29") (pin "1") (pinfunction "1_1") (pintype "passive"))
      (node (ref "C30") (pin "1") (pinfunction "1_1") (pintype "passive"))
      (node (ref "C53") (pin "1") (pinfunction "1_1") (pintype "passive"))
      (node (ref "C54") (pin "1") (pinfunction "1_1") (pintype "passive"))
      (node (ref "C55") (pin "1") (pinfunction "1_1") (pintype "passive"))
      (node (ref "C56") (pin "1") (pinfunction "1_1") (pintype "passive"))
      (node (ref "C57") (pin "2") (pinfunction "2_2") (pintype "passive"))
      (node (ref "C6") (pin "1") (pinfunction "1_1") (pintype "passive"))
      (node (ref "C7") (pin "2") (pinfunction "2_2") (pintype "passive"))
      (node (ref "IC1") (pin "6") (pinfunction "V_IO_6") (pintype "power_in"))
      (node (ref "IC2") (pin "6") (pinfunction "V_IO_6") (pintype "power_in"))
      (node (ref "L11") (pin "2") (pinfunction "2_2") (pintype "passive"))
      (node (ref "OOBDPICAN") (pin "1") (pinfunction "1_1") (pintype "passive"))
      (node (ref "R70") (pin "2") (pinfunction "2_2") (pintype "passive"))
      (node (ref "R86") (pin "1") (pinfunction "1_1") (pintype "passive"))
      (node (ref "TLV320AIC3107") (pin "25") (pinfunction "SPVDD_25") (pintype "bidirectional"))
      (node (ref "U1") (pin "5") (pinfunction "IN_5") (pintype "power_in"))
      (node (ref "U3") (pin "5") (pinfunction "IN_5") (pintype "power_in"))
    )
    (net (code "3") (name "+5V_OTG_PWR") (class "Default")
      (node (ref "C4") (pin "1") (pinfunction "1_1") (pintype "passive"))
      (node (ref "L1") (pin "1") (pinfunction "1_1") (pintype "passive"))
      (node (ref "USB_OTG") (pin "VBUS") (pinfunction "VBUS_VBUS") (pintype "power_in"))
    )
    (net (code "4") (name "+12V") (class "Default")
      (node (ref "C51") (pin "+") (pinfunction "+_+") (pintype "passive"))
      (node (ref "D4") (pin "C") (pinfunction "C_C") (pintype "passive"))
      (node (ref "OOBD2-CONNECTOR") (pin "10") (pinfunction "10_10") (pintype "passive"))
      (node (ref "R69") (pin "1") (pinfunction "1_1") (pintype "passive"))
      (node (ref "U10") (pin "2") (pinfunction "IN_2") (pintype "bidirectional"))
    )
    (net (code "5") (name "3V3") (class "Default")
      (node (ref "AM3352-SOM-EVB-PLATFORM") (pin "3-3") (pinfunction "3.3V_3-3") (pintype "passive"))
      (node (ref "AM3352-SOM-EVB-PLATFORM") (pin "4-3") (pinfunction "3.3V_4-3") (pintype "passive"))
    )
    (net (code "6") (name "AGND") (class "Default")
      (node (ref "C18") (pin "2") (pinfunction "2_2") (pintype "passive"))
      (node (ref "C19") (pin "1") (pinfunction "1_1") (pintype "passive"))
      (node (ref "TLV320AIC3107") (pin "11") (pinfunction "AVSS_ADC_11") (pintype "bidirectional"))
      (node (ref "TLV320AIC3107") (pin "22") (pinfunction "AVSS_DAC_22") (pintype "bidirectional"))
    )
    (net (code "7") (name "AUD_BCLK") (class "Default")
      (node (ref "AM3352-SOM-EVB-PLATFORM") (pin "4-19") (pinfunction "P3_14/SPI1_CLK_4-19") (pintype "passive"))
      (node (ref "R15") (pin "1") (pinfunction "1_1") (pintype "passive"))
    )
    (net (code "8") (name "AUD_DIN") (class "Default")
      (node (ref "AM3352-SOM-EVB-PLATFORM") (pin "4-18") (pinfunction "P3_16/SPI1_D1(MOSI)_4-18") (pintype "passive"))
      (node (ref "R16") (pin "1") (pinfunction "1_1") (pintype "passive"))
    )
    (net (code "9") (name "AUD_DOUT") (class "Default")
      (node (ref "AM3352-SOM-EVB-PLATFORM") (pin "4-20") (pinfunction "P3_17/SPI1_CS0_4-20") (pintype "passive"))
      (node (ref "R17") (pin "1") (pinfunction "1_1") (pintype "passive"))
    )
    (net (code "10") (name "AUD_MCLK") (class "Default")
      (node (ref "AM3352-SOM-EVB-PLATFORM") (pin "4-24") (pinfunction "P3_21/LED3_4-24") (pintype "passive"))
      (node (ref "R18") (pin "1") (pinfunction "1_1") (pintype "passive"))
    )
    (net (code "11") (name "AUD_WCLK") (class "Default")
      (node (ref "AM3352-SOM-EVB-PLATFORM") (pin "4-17") (pinfunction "P3_15/SPI1_D0(MISO)_4-17") (pintype "passive"))
      (node (ref "R10") (pin "1") (pinfunction "1_1") (pintype "passive"))
    )
    (net (code "12") (name "CAN0_H") (class "Default")
      (node (ref "D1") (pin "2") (pinfunction "C2_2") (pintype "bidirectional"))
      (node (ref "IC2") (pin "17") (pinfunction "CAN_H_17") (pintype "bidirectional"))
      (node (ref "OOBD2-CONNECTOR") (pin "1") (pinfunction "1_1") (pintype "passive"))
      (node (ref "R27") (pin "1") (pinfunction "1_1") (pintype "passive"))
      (node (ref "R6") (pin "2") (pinfunction "2_2") (pintype "passive"))
    )
    (net (code "13") (name "CAN0_L") (class "Default")
      (node (ref "D1") (pin "1") (pinfunction "C1_1") (pintype "bidirectional"))
      (node (ref "IC2") (pin "15") (pinfunction "CAN_L_15") (pintype "bidirectional"))
      (node (ref "MS-CAN") (pin "2") (pinfunction "2_2") (pintype "passive"))
      (node (ref "OOBD2-CONNECTOR") (pin "2") (pinfunction "2_2") (pintype "passive"))
      (node (ref "R28") (pin "1") (pinfunction "1_1") (pintype "passive"))
    )
    (net (code "14") (name "CAN1_H") (class "Default")
      (node (ref "D2") (pin "2") (pinfunction "C2_2") (pintype "bidirectional"))
      (node (ref "IC1") (pin "17") (pinfunction "CAN_H_17") (pintype "bidirectional"))
      (node (ref "OOBD2-CONNECTOR") (pin "7") (pinfunction "7_7") (pintype "passive"))
      (node (ref "R29") (pin "2") (pinfunction "2_2") (pintype "passive"))
      (node (ref "R31") (pin "2") (pinfunction "2_2") (pintype "passive"))
    )
    (net (code "15") (name "CAN1_L") (class "Default")
      (node (ref "D2") (pin "1") (pinfunction "C1_1") (pintype "bidirectional"))
      (node (ref "HS-CAN") (pin "2") (pinfunction "2_2") (pintype "passive"))
      (node (ref "IC1") (pin "15") (pinfunction "CAN_L_15") (pintype "bidirectional"))
      (node (ref "OOBD2-CONNECTOR") (pin "6") (pinfunction "6_6") (pintype "passive"))
      (node (ref "R30") (pin "1") (pinfunction "1_1") (pintype "passive"))
    )
    (net (code "16") (name "DCAN0_RX") (class "Default")
      (node (ref "AM3352-SOM-EVB-PLATFORM") (pin "4-7") (pinfunction "P0_13/I2C2_SCL_4-7") (pintype "passive"))
      (node (ref "IC2") (pin "4") (pinfunction "RXD_4") (pintype "output"))
      (node (ref "U6") (pin "4") (pinfunction "RXD_4") (pintype "output"))
    )
    (net (code "17") (name "DCAN0_TX") (class "Default")
      (node (ref "AM3352-SOM-EVB-PLATFORM") (pin "4-8") (pinfunction "P0_12/I2C2_SDA_4-8") (pintype "passive"))
      (node (ref "IC2") (pin "5") (pinfunction "TXD_5") (pintype "input"))
      (node (ref "U6") (pin "1") (pinfunction "TXD_1") (pintype "input"))
    )
    (net (code "18") (name "DCAN1_RX") (class "Default")
      (node (ref "AM3352-SOM-EVB-PLATFORM") (pin "4-13") (pinfunction "P1_9/UART4_TXD_4-13") (pintype "passive"))
      (node (ref "IC1") (pin "4") (pinfunction "RXD_4") (pintype "output"))
      (node (ref "U2") (pin "4") (pinfunction "RXD_4") (pintype "output"))
    )
    (net (code "19") (name "DCAN1_TX") (class "Default")
      (node (ref "AM3352-SOM-EVB-PLATFORM") (pin "4-14") (pinfunction "P1_8/UART4_RXD_4-14") (pintype "passive"))
      (node (ref "IC1") (pin "5") (pinfunction "TXD_5") (pintype "input"))
      (node (ref "U2") (pin "1") (pinfunction "TXD_1") (pintype "input"))
    )
    (net (code "20") (name "DVDD") (class "Default")
      (node (ref "C36") (pin "2") (pinfunction "2_2") (pintype "passive"))
      (node (ref "C38") (pin "2") (pinfunction "2_2") (pintype "passive"))
      (node (ref "C44") (pin "2") (pinfunction "2_2") (pintype "passive"))
      (node (ref "TLV320AIC3107") (pin "33") (pinfunction "DVDD_33") (pintype "bidirectional"))
      (node (ref "U4") (pin "5") (pinfunction "OUT_5") (pintype "passive"))
    )
    (net (code "21") (name "EXT_WAKEUP") (class "Default")
      (node (ref "AM3352-SOM-EVB-PLATFORM") (pin "3-20") (pinfunction "EXT_WAKEUP_3-20") (pintype "passive"))
      (node (ref "R54") (pin "1") (pinfunction "1_1") (pintype "passive"))
    )
    (net (code "22") (name "GND") (class "Default")
      (node (ref "AM3352-SOM-EVB-PLATFORM") (pin "3-2") (pinfunction "GND_3-2") (pintype "passive"))
      (node (ref "AM3352-SOM-EVB-PLATFORM") (pin "3-4") (pinfunction "GND_3-4") (pintype "passive"))
      (node (ref "AM3352-SOM-EVB-PLATFORM") (pin "4-2") (pinfunction "GND_4-2") (pintype "passive"))
      (node (ref "AM3352-SOM-EVB-PLATFORM") (pin "4-4") (pinfunction "GND_4-4") (pintype "passive"))
      (node (ref "AM3352-SOM-EVB-PLATFORM") (pin "4-40") (pinfunction "GNDA_4-40") (pintype "passive"))
      (node (ref "BAT2") (pin "GND") (pinfunction "-_GND") (pintype "power_in"))
      (node (ref "C1") (pin "2") (pinfunction "2_2") (pintype "passive"))
      (node (ref "C10") (pin "2") (pinfunction "2_2") (pintype "passive"))
      (node (ref "C11") (pin "2") (pinfunction "2_2") (pintype "passive"))
      (node (ref "C12") (pin "2") (pinfunction "2_2") (pintype "passive"))
      (node (ref "C13") (pin "2") (pinfunction "2_2") (pintype "passive"))
      (node (ref "C14") (pin "2") (pinfunction "2_2") (pintype "passive"))
      (node (ref "C16") (pin "2") (pinfunction "2_2") (pintype "passive"))
      (node (ref "C17") (pin "2") (pinfunction "2_2") (pintype "passive"))
      (node (ref "C2") (pin "2") (pinfunction "2_2") (pintype "passive"))
      (node (ref "C27") (pin "2") (pinfunction "2_2") (pintype "passive"))
      (node (ref "C28") (pin "2") (pinfunction "2_2") (pintype "passive"))
      (node (ref "C29") (pin "2") (pinfunction "2_2") (pintype "passive"))
      (node (ref "C3") (pin "2") (pinfunction "2_2") (pintype "passive"))
      (node (ref "C30") (pin "2") (pinfunction "2_2") (pintype "passive"))
      (node (ref "C31") (pin "2") (pinfunction "2_2") (pintype "passive"))
      (node (ref "C32") (pin "2") (pinfunction "2_2") (pintype "passive"))
      (node (ref "C35") (pin "1") (pinfunction "1_1") (pintype "passive"))
      (node (ref "C36") (pin "1") (pinfunction "1_1") (pintype "passive"))
      (node (ref "C37") (pin "1") (pinfunction "1_1") (pintype "passive"))
      (node (ref "C38") (pin "1") (pinfunction "1_1") (pintype "passive"))
      (node (ref "C39") (pin "2") (pinfunction "2_2") (pintype "passive"))
      (node (ref "C4") (pin "2") (pinfunction "2_2") (pintype "passive"))
      (node (ref "C40") (pin "2") (pinfunction "2_2") (pintype "passive"))
      (node (ref "C41") (pin "2") (pinfunction "2_2") (pintype "passive"))
      (node (ref "C42") (pin "2") (pinfunction "2_2") (pintype "passive"))
      (node (ref "C43") (pin "1") (pinfunction "1_1") (pintype "passive"))
      (node (ref "C44") (pin "1") (pinfunction "1_1") (pintype "passive"))
      (node (ref "C47") (pin "2") (pinfunction "2_2") (pintype "passive"))
      (node (ref "C48") (pin "2") (pinfunction "2_2") (pintype "passive"))
      (node (ref "C5") (pin "1") (pinfunction "1_1") (pintype "passive"))
      (node (ref "C51") (pin "-") (pinfunction "-_-") (pintype "passive"))
      (node (ref "C52") (pin "2") (pinfunction "2_2") (pintype "passive"))
      (node (ref "C53") (pin "2") (pinfunction "2_2") (pintype "passive"))
      (node (ref "C54") (pin "2") (pinfunction "2_2") (pintype "passive"))
      (node (ref "C55") (pin "2") (pinfunction "2_2") (pintype "passive"))
      (node (ref "C56") (pin "2") (pinfunction "2_2") (pintype "passive"))
      (node (ref "C57") (pin "1") (pinfunction "1_1") (pintype "passive"))
      (node (ref "C6") (pin "2") (pinfunction "2_2") (pintype "passive"))
      (node (ref "C63") (pin "2") (pinfunction "2_2") (pintype "passive"))
      (node (ref "C64") (pin "2") (pinfunction "2_2") (pintype "passive"))
      (node (ref "C7") (pin "1") (pinfunction "1_1") (pintype "passive"))
      (node (ref "C8") (pin "2") (pinfunction "2_2") (pintype "passive"))
      (node (ref "C9") (pin "1") (pinfunction "1_1") (pintype "passive"))
      (node (ref "D4") (pin "A") (pinfunction "A_A") (pintype "passive"))
      (node (ref "IC1") (pin "1") (pinfunction "GND1_1") (pintype "power_in"))
      (node (ref "IC1") (pin "10") (pinfunction "GND1_10") (pintype "power_in"))
      (node (ref "IC1") (pin "3") (pinfunction "GND1_3") (pintype "power_in"))
      (node (ref "IC1") (pin "7") (pinfunction "GND1_7") (pintype "power_in"))
      (node (ref "IC1") (pin "9") (pinfunction "GND1_9") (pintype "power_in"))
      (node (ref "IC2") (pin "1") (pinfunction "GND1_1") (pintype "power_in"))
      (node (ref "IC2") (pin "10") (pinfunction "GND1_10") (pintype "power_in"))
      (node (ref "IC2") (pin "3") (pinfunction "GND1_3") (pintype "power_in"))
      (node (ref "IC2") (pin "7") (pinfunction "GND1_7") (pintype "power_in"))
      (node (ref "IC2") (pin "9") (pinfunction "GND1_9") (pintype "power_in"))
      (node (ref "IC4") (pin "10") (pinfunction "NC_10") (pintype "bidirectional"))
      (node (ref "IC4") (pin "11") (pinfunction "NC_11") (pintype "bidirectional"))
      (node (ref "IC4") (pin "12") (pinfunction "NC_12") (pintype "bidirectional"))
      (node (ref "IC4") (pin "13") (pinfunction "GND_13") (pintype "bidirectional"))
      (node (ref "IC4") (pin "5") (pinfunction "NC_5") (pintype "bidirectional"))
      (node (ref "IC4") (pin "6") (pinfunction "NC_6") (pintype "bidirectional"))
      (node (ref "IC4") (pin "7") (pinfunction "NC_7") (pintype "bidirectional"))
      (node (ref "IC4") (pin "8") (pinfunction "NC_8") (pintype "bidirectional"))
      (node (ref "IC4") (pin "9") (pinfunction "NC_9") (pintype "bidirectional"))
      (node (ref "L3") (pin "1") (pinfunction "1_1") (pintype "passive"))
      (node (ref "L6") (pin "1") (pinfunction "1_1") (pintype "passive"))
      (node (ref "LED2") (pin "C") (pinfunction "C_C") (pintype "passive"))
      (node (ref "LED3") (pin "C") (pinfunction "C_C") (pintype "passive"))
      (node (ref "OOBD2-CONNECTOR") (pin "3") (pinfunction "3_3") (pintype "passive"))
      (node (ref "OOBDPICAN") (pin "5") (pinfunction "5_5") (pintype "passive"))
      (node (ref "PWR_LED") (pin "C") (pinfunction "C_C") (pintype "passive"))
      (node (ref "R12") (pin "2") (pinfunction "2_2") (pintype "passive"))
      (node (ref "R14") (pin "1") (pinfunction "1_1") (pintype "passive"))
      (node (ref "R19") (pin "1") (pinfunction "1_1") (pintype "passive"))
      (node (ref "R21") (pin "1") (pinfunction "1_1") (pintype "passive"))
      (node (ref "R24") (pin "1") (pinfunction "1_1") (pintype "passive"))
      (node (ref "R3") (pin "1") (pinfunction "1_1") (pintype "passive"))
      (node (ref "R4") (pin "1") (pinfunction "1_1") (pintype "passive"))
      (node (ref "R41") (pin "2") (pinfunction "2_2") (pintype "passive"))
      (node (ref "R5") (pin "2") (pinfunction "2_2") (pintype "passive"))
      (node (ref "R55") (pin "2") (pinfunction "2_2") (pintype "passive"))
      (node (ref "R84") (pin "2") (pinfunction "2_2") (pintype "passive"))
      (node (ref "R85") (pin "2") (pinfunction "2_2") (pintype "passive"))
      (node (ref "TLV320AIC3107") (pin "16") (pinfunction "DRVSS_16") (pintype "bidirectional"))
      (node (ref "TLV320AIC3107") (pin "24") (pinfunction "SPVSS_24") (pintype "bidirectional"))
      (node (ref "TLV320AIC3107") (pin "26") (pinfunction "SPOP_26") (pintype "bidirectional"))
      (node (ref "TLV320AIC3107") (pin "39") (pinfunction "DVSS_39") (pintype "bidirectional"))
      (node (ref "U1") (pin "2") (pinfunction "GND_2") (pintype "power_in"))
      (node (ref "U10") (pin "4") (pinfunction "GND_4") (pintype "bidirectional"))
      (node (ref "U2") (pin "2") (pinfunction "VSS_2") (pintype "power_in"))
      (node (ref "U3") (pin "2") (pinfunction "GND_2") (pintype "power_in"))
      (node (ref "U4") (pin "2") (pinfunction "GND_2") (pintype "input"))
      (node (ref "U6") (pin "2") (pinfunction "VSS_2") (pintype "power_in"))
      (node (ref "USB_HOST") (pin "4") (pinfunction "4_4") (pintype "passive"))
      (node (ref "USB_OTG") (pin "GND") (pinfunction "GND_GND") (pintype "power_in"))
    )
    (net (code "23") (name "GNDA") (class "Default")
      (node (ref "C15") (pin "2") (pinfunction "2_2") (pintype "passive"))
      (node (ref "C20") (pin "2") (pinfunction "2_2") (pintype "passive"))
      (node (ref "C21") (pin "2") (pinfunction "2_2") (pintype "passive"))
      (node (ref "C22") (pin "2") (pinfunction "2_2") (pintype "passive"))
      (node (ref "C23") (pin "2") (pinfunction "2_2") (pintype "passive"))
      (node (ref "C24") (pin "2") (pinfunction "2_2") (pintype "passive"))
      (node (ref "C25") (pin "2") (pinfunction "2_2") (pintype "passive"))
      (node (ref "C26") (pin "2") (pinfunction "2_2") (pintype "passive"))
      (node (ref "C31") (pin "1") (pinfunction "1_1") (pintype "passive"))
      (node (ref "C32") (pin "1") (pinfunction "1_1") (pintype "passive"))
      (node (ref "C33") (pin "2") (pinfunction "2_2") (pintype "passive"))
      (node (ref "C34") (pin "2") (pinfunction "2_2") (pintype "passive"))
      (node (ref "D1") (pin "3") (pinfunction "CC_3") (pintype "bidirectional"))
      (node (ref "D2") (pin "3") (pinfunction "CC_3") (pintype "bidirectional"))
      (node (ref "IC1") (pin "11") (pinfunction "GND2_11") (pintype "power_in"))
      (node (ref "IC1") (pin "13") (pinfunction "GND2_13") (pintype "power_in"))
      (node (ref "IC1") (pin "16") (pinfunction "GND2_16") (pintype "power_in"))
      (node (ref "IC1") (pin "20") (pinfunction "GND2_20") (pintype "power_in"))
      (node (ref "IC2") (pin "11") (pinfunction "GND2_11") (pintype "power_in"))
      (node (ref "IC2") (pin "13") (pinfunction "GND2_13") (pintype "power_in"))
      (node (ref "IC2") (pin "16") (pinfunction "GND2_16") (pintype "power_in"))
      (node (ref "IC2") (pin "20") (pinfunction "GND2_20") (pintype "power_in"))
      (node (ref "R25") (pin "1") (pinfunction "1_1") (pintype "passive"))
      (node (ref "R26") (pin "1") (pinfunction "1_1") (pintype "passive"))
    )
    (net (code "24") (name "HS-CAN_RS") (class "Default")
      (node (ref "AM3352-SOM-EVB-PLATFORM") (pin "4-26") (pinfunction "P3_8/EMU1_4-26") (pintype "passive"))
      (node (ref "R7") (pin "2") (pinfunction "2_2") (pintype "passive"))
    )
    (net (code "25") (name "I2C0-SCL") (class "Default")
      (node (ref "AM3352-SOM-EVB-PLATFORM") (pin "4-15") (pinfunction "P3_6/I2C0-SCL_4-15") (pintype "passive"))
      (node (ref "IC4") (pin "16") (pinfunction "SCL_16") (pintype "bidirectional"))
      (node (ref "R8") (pin "1") (pinfunction "1_1") (pintype "passive"))
      (node (ref "TLV320AIC3107") (pin "1") (pinfunction "SCL_1") (pintype "bidirectional"))
    )
    (net (code "26") (name "I2C0-SDA") (class "Default")
      (node (ref "AM3352-SOM-EVB-PLATFORM") (pin "4-16") (pinfunction "P3_5/I2C0-SDA_4-16") (pintype "passive"))
      (node (ref "IC4") (pin "15") (pinfunction "SDA_15") (pintype "bidirectional"))
      (node (ref "R9") (pin "1") (pinfunction "1_1") (pintype "passive"))
      (node (ref "TLV320AIC3107") (pin "2") (pinfunction "SDA_2") (pintype "bidirectional"))
    )
    (net (code "27") (name "LED1") (class "Default")
      (node (ref "AM3352-SOM-EVB-PLATFORM") (pin "4-21") (pinfunction "P3_18/LED1_4-21") (pintype "passive"))
      (node (ref "R48") (pin "1") (pinfunction "1_1") (pintype "passive"))
    )
    (net (code "28") (name "LED2") (class "Default")
      (node (ref "AM3352-SOM-EVB-PLATFORM") (pin "4-23") (pinfunction "P3_20/LED2_4-23") (pintype "passive"))
      (node (ref "R49") (pin "1") (pinfunction "1_1") (pintype "passive"))
    )
    (net (code "29") (name "MS-CAN_RS") (class "Default")
      (node (ref "AM3352-SOM-EVB-PLATFORM") (pin "4-25") (pinfunction "P3_7/EMU0_4-25") (pintype "passive"))
      (node (ref "R40") (pin "2") (pinfunction "2_2") (pintype "passive"))
    )
    (net (code "30") (name "Net-(BAT2-+)") (class "Default")
      (node (ref "BAT2") (pin "VCC@1") (pinfunction "+_VCC@1") (pintype "power_in"))
      (node (ref "IC4") (pin "14") (pinfunction "VBAT_14") (pintype "bidirectional"))
    )
    (net (code "31") (name "Net-(C3-Pad1)") (class "Default")
      (node (ref "C3") (pin "1") (pinfunction "1_1") (pintype "passive"))
      (node (ref "L5") (pin "2") (pinfunction "2_2") (pintype "passive"))
      (node (ref "USB_HOST") (pin "1") (pinfunction "1_1") (pintype "passive"))
    )
    (net (code "32") (name "Net-(C18-Pad1)") (class "Default")
      (node (ref "C18") (pin "1") (pinfunction "1_1") (pintype "passive"))
      (node (ref "R13") (pin "2") (pinfunction "2_2") (pintype "passive"))
      (node (ref "SPEAKER") (pin "2") (pinfunction "2_2") (pintype "passive"))
    )
    (net (code "33") (name "Net-(C19-Pad2)") (class "Default")
      (node (ref "C19") (pin "2") (pinfunction "2_2") (pintype "passive"))
      (node (ref "L4") (pin "2") (pinfunction "2_2") (pintype "passive"))
      (node (ref "R14") (pin "2") (pinfunction "2_2") (pintype "passive"))
    )
    (net (code "34") (name "Net-(C33-Pad1)") (class "Default")
      (node (ref "C33") (pin "1") (pinfunction "1_1") (pintype "passive"))
      (node (ref "R31") (pin "1") (pinfunction "1_1") (pintype "passive"))
      (node (ref "R32") (pin "1") (pinfunction "1_1") (pintype "passive"))
    )
    (net (code "35") (name "Net-(C34-Pad1)") (class "Default")
      (node (ref "C34") (pin "1") (pinfunction "1_1") (pintype "passive"))
      (node (ref "R33") (pin "1") (pinfunction "1_1") (pintype "passive"))
      (node (ref "R6") (pin "1") (pinfunction "1_1") (pintype "passive"))
    )
    (net (code "36") (name "Net-(C45-Pad1)") (class "Default")
      (node (ref "C45") (pin "1") (pinfunction "1_1") (pintype "passive"))
      (node (ref "C46") (pin "1") (pinfunction "1_1") (pintype "passive"))
    )
    (net (code "37") (name "Net-(C48-Pad1)") (class "Default")
      (node (ref "C48") (pin "1") (pinfunction "1_1") (pintype "passive"))
      (node (ref "R54") (pin "2") (pinfunction "2_2") (pintype "passive"))
      (node (ref "R55") (pin "1") (pinfunction "1_1") (pintype "passive"))
      (node (ref "WAKE-UP") (pin "2") (pinfunction "2_2") (pintype "passive"))
    )
    (net (code "38") (name "Net-(C50-Pad2)") (class "Default")
      (node (ref "C50") (pin "2") (pinfunction "2_2") (pintype "passive"))
      (node (ref "R84") (pin "1") (pinfunction "1_1") (pintype "passive"))
    )
    (net (code "39") (name "Net-(HS-CAN-Pad1)") (class "Default")
      (node (ref "HS-CAN") (pin "1") (pinfunction "1_1") (pintype "passive"))
      (node (ref "R32") (pin "2") (pinfunction "2_2") (pintype "passive"))
    )
    (net (code "40") (name "Net-(IC1-R_S)") (class "Default")
      (node (ref "IC1") (pin "18") (pinfunction "R_S_18") (pintype "passive"))
      (node (ref "R26") (pin "2") (pinfunction "2_2") (pintype "passive"))
    )
    (net (code "41") (name "Net-(IC1-V_ISOIN)") (class "Default")
      (node (ref "C23") (pin "1") (pinfunction "1_1") (pintype "passive"))
      (node (ref "C24") (pin "1") (pinfunction "1_1") (pintype "passive"))
      (node (ref "C25") (pin "1") (pinfunction "1_1") (pintype "passive"))
      (node (ref "C26") (pin "1") (pinfunction "1_1") (pintype "passive"))
      (node (ref "IC1") (pin "12") (pinfunction "V_ISOOUT_12") (pintype "output"))
      (node (ref "IC1") (pin "19") (pinfunction "V_ISOIN_19") (pintype "input"))
    )
    (net (code "42") (name "Net-(IC2-R_S)") (class "Default")
      (node (ref "IC2") (pin "18") (pinfunction "R_S_18") (pintype "passive"))
      (node (ref "R25") (pin "2") (pinfunction "2_2") (pintype "passive"))
    )
    (net (code "43") (name "Net-(IC2-V_ISOIN)") (class "Default")
      (node (ref "C15") (pin "1") (pinfunction "1_1") (pintype "passive"))
      (node (ref "C20") (pin "1") (pinfunction "1_1") (pintype "passive"))
      (node (ref "C21") (pin "1") (pinfunction "1_1") (pintype "passive"))
      (node (ref "C22") (pin "1") (pinfunction "1_1") (pintype "passive"))
      (node (ref "IC2") (pin "12") (pinfunction "V_ISOOUT_12") (pintype "output"))
      (node (ref "IC2") (pin "19") (pinfunction "V_ISOIN_19") (pintype "input"))
    )
    (net (code "44") (name "Net-(IC4-~{INT})") (class "Default")
      (node (ref "IC4") (pin "3") (pinfunction "~{INT}_3") (pintype "bidirectional"))
      (node (ref "R20") (pin "1") (pinfunction "1_1") (pintype "passive"))
    )
    (net (code "45") (name "Net-(L3-Pad2)") (class "Default")
      (node (ref "L3") (pin "2") (pinfunction "2_2") (pintype "passive"))
      (node (ref "USB_OTG") (pin "GND1") (pinfunction "GND1_GND1") (pintype "input"))
      (node (ref "USB_OTG") (pin "GND2") (pinfunction "GND2_GND2") (pintype "input"))
      (node (ref "USB_OTG") (pin "GND3") (pinfunction "GND3_GND3") (pintype "input"))
      (node (ref "USB_OTG") (pin "GND4") (pinfunction "GND4_GND4") (pintype "input"))
    )
    (net (code "46") (name "Net-(L4-Pad1)") (class "Default")
      (node (ref "L4") (pin "1") (pinfunction "1_1") (pintype "passive"))
      (node (ref "SPEAKER") (pin "1") (pinfunction "1_1") (pintype "passive"))
    )
    (net (code "47") (name "Net-(LED2-PadA)") (class "Default")
      (node (ref "LED2") (pin "A") (pinfunction "A_A") (pintype "passive"))
      (node (ref "R49") (pin "2") (pinfunction "2_2") (pintype "passive"))
    )
    (net (code "48") (name "Net-(LED3-PadA)") (class "Default")
      (node (ref "LED3") (pin "A") (pinfunction "A_A") (pintype "passive"))
      (node (ref "R48") (pin "2") (pinfunction "2_2") (pintype "passive"))
    )
    (net (code "49") (name "Net-(MS-CAN-Pad1)") (class "Default")
      (node (ref "MS-CAN") (pin "1") (pinfunction "1_1") (pintype "passive"))
      (node (ref "R33") (pin "2") (pinfunction "2_2") (pintype "passive"))
    )
    (net (code "50") (name "Net-(PWR_LED-PadA)") (class "Default")
      (node (ref "PWR_LED") (pin "A") (pinfunction "A_A") (pintype "passive"))
      (node (ref "R86") (pin "2") (pinfunction "2_2") (pintype "passive"))
    )
    (net (code "51") (name "Net-(R47-Pad1)") (class "Default")
      (node (ref "R47") (pin "1") (pinfunction "1_1") (pintype "passive"))
      (node (ref "WAKE-UP") (pin "1") (pinfunction "1_1") (pintype "passive"))
    )
    (net (code "52") (name "Net-(TLV320AIC3107-BCLK)") (class "Default")
      (node (ref "R15") (pin "2") (pinfunction "2_2") (pintype "passive"))
      (node (ref "TLV320AIC3107") (pin "35") (pinfunction "BCLK_35") (pintype "bidirectional"))
    )
    (net (code "53") (name "Net-(TLV320AIC3107-DIN)") (class "Default")
      (node (ref "R16") (pin "2") (pinfunction "2_2") (pintype "passive"))
      (node (ref "TLV320AIC3107") (pin "37") (pinfunction "DIN_37") (pintype "bidirectional"))
    )
    (net (code "54") (name "Net-(TLV320AIC3107-DOUT)") (class "Default")
      (node (ref "R17") (pin "2") (pinfunction "2_2") (pintype "passive"))
      (node (ref "TLV320AIC3107") (pin "38") (pinfunction "DOUT_38") (pintype "bidirectional"))
    )
    (net (code "55") (name "Net-(TLV320AIC3107-IOVDD)") (class "Default")
      (node (ref "C45") (pin "2") (pinfunction "2_2") (pintype "passive"))
      (node (ref "C46") (pin "2") (pinfunction "2_2") (pintype "passive"))
      (node (ref "TLV320AIC3107") (pin "40") (pinfunction "IOVDD_40") (pintype "bidirectional"))
    )
    (net (code "56") (name "Net-(TLV320AIC3107-MCLK)") (class "Default")
      (node (ref "R18") (pin "2") (pinfunction "2_2") (pintype "passive"))
      (node (ref "TLV320AIC3107") (pin "34") (pinfunction "MCLK_34") (pintype "bidirectional"))
    )
    (net (code "57") (name "Net-(TLV320AIC3107-SPOM)") (class "Default")
      (node (ref "R11") (pin "2") (pinfunction "2_2") (pintype "passive"))
      (node (ref "R13") (pin "1") (pinfunction "1_1") (pintype "passive"))
      (node (ref "TLV320AIC3107") (pin "23") (pinfunction "SPOM_23") (pintype "bidirectional"))
    )
    (net (code "58") (name "Net-(TLV320AIC3107-SWOUTM)") (class "Default")
      (node (ref "R11") (pin "1") (pinfunction "1_1") (pintype "passive"))
      (node (ref "TLV320AIC3107") (pin "28") (pinfunction "SWOUTM_28") (pintype "bidirectional"))
    )
    (net (code "59") (name "Net-(TLV320AIC3107-SWOUTP)") (class "Default")
      (node (ref "R12") (pin "1") (pinfunction "1_1") (pintype "passive"))
      (node (ref "TLV320AIC3107") (pin "29") (pinfunction "SWOUTP_29") (pintype "bidirectional"))
    )
    (net (code "60") (name "Net-(TLV320AIC3107-WCLK)") (class "Default")
      (node (ref "R10") (pin "2") (pinfunction "2_2") (pintype "passive"))
      (node (ref "TLV320AIC3107") (pin "36") (pinfunction "WCLK_36") (pintype "bidirectional"))
    )
    (net (code "61") (name "Net-(U1-ISET)") (class "Default")
      (node (ref "R3") (pin "2") (pinfunction "2_2") (pintype "passive"))
      (node (ref "U1") (pin "3") (pinfunction "ISET_3") (pintype "bidirectional"))
    )
    (net (code "62") (name "Net-(U1-OUT)") (class "Default")
      (node (ref "C63") (pin "1") (pinfunction "1_1") (pintype "passive"))
      (node (ref "C64") (pin "1") (pinfunction "1_1") (pintype "passive"))
      (node (ref "L1") (pin "2") (pinfunction "2_2") (pintype "passive"))
      (node (ref "R1") (pin "2") (pinfunction "2_2") (pintype "passive"))
      (node (ref "U1") (pin "1") (pinfunction "OUT_1") (pintype "bidirectional"))
    )
    (net (code "63") (name "Net-(U2-CANH)") (class "Default")
      (node (ref "R29") (pin "1") (pinfunction "1_1") (pintype "passive"))
      (node (ref "U2") (pin "7") (pinfunction "CANH_7") (pintype "output"))
    )
    (net (code "64") (name "Net-(U2-CANL)") (class "Default")
      (node (ref "R30") (pin "2") (pinfunction "2_2") (pintype "passive"))
      (node (ref "U2") (pin "6") (pinfunction "CANL_6") (pintype "output"))
    )
    (net (code "65") (name "Net-(U2-RS)") (class "Default")
      (node (ref "R5") (pin "1") (pinfunction "1_1") (pintype "passive"))
      (node (ref "R7") (pin "1") (pinfunction "1_1") (pintype "passive"))
      (node (ref "U2") (pin "8") (pinfunction "RS_8") (pintype "input"))
    )
    (net (code "66") (name "Net-(U3-ISET)") (class "Default")
      (node (ref "R19") (pin "2") (pinfunction "2_2") (pintype "passive"))
      (node (ref "U3") (pin "3") (pinfunction "ISET_3") (pintype "bidirectional"))
    )
    (net (code "67") (name "Net-(U3-OUT)") (class "Default")
      (node (ref "C10") (pin "1") (pinfunction "1_1") (pintype "passive"))
      (node (ref "C8") (pin "1") (pinfunction "1_1") (pintype "passive"))
      (node (ref "L5") (pin "1") (pinfunction "1_1") (pintype "passive"))
      (node (ref "R22") (pin "2") (pinfunction "2_2") (pintype "passive"))
      (node (ref "U3") (pin "1") (pinfunction "OUT_1") (pintype "bidirectional"))
    )
    (net (code "68") (name "Net-(U4-BP)") (class "Default")
      (node (ref "C37") (pin "2") (pinfunction "2_2") (pintype "passive"))
      (node (ref "U4") (pin "4") (pinfunction "BP_4") (pintype "input"))
    )
    (net (code "69") (name "Net-(U6-CANH)") (class "Default")
      (node (ref "R27") (pin "2") (pinfunction "2_2") (pintype "passive"))
      (node (ref "U6") (pin "7") (pinfunction "CANH_7") (pintype "output"))
    )
    (net (code "70") (name "Net-(U6-CANL)") (class "Default")
      (node (ref "R28") (pin "2") (pinfunction "2_2") (pintype "passive"))
      (node (ref "U6") (pin "6") (pinfunction "CANL_6") (pintype "output"))
    )
    (net (code "71") (name "Net-(U6-RS)") (class "Default")
      (node (ref "R40") (pin "1") (pinfunction "1_1") (pintype "passive"))
      (node (ref "R41") (pin "1") (pinfunction "1_1") (pintype "passive"))
      (node (ref "U6") (pin "8") (pinfunction "RS_8") (pintype "input"))
    )
    (net (code "72") (name "Net-(U10-BS)") (class "Default")
      (node (ref "C49") (pin "1") (pinfunction "1_1") (pintype "passive"))
      (node (ref "U10") (pin "1") (pinfunction "BS_1") (pintype "bidirectional"))
    )
    (net (code "73") (name "Net-(U10-COMP)") (class "Default")
      (node (ref "C50") (pin "1") (pinfunction "1_1") (pintype "passive"))
      (node (ref "U10") (pin "6") (pinfunction "COMP_6") (pintype "bidirectional"))
    )
    (net (code "74") (name "Net-(U10-EN)") (class "Default")
      (node (ref "R69") (pin "2") (pinfunction "2_2") (pintype "passive"))
      (node (ref "U10") (pin "7") (pinfunction "EN_7") (pintype "bidirectional"))
    )
    (net (code "75") (name "Net-(U10-FB)") (class "Default")
      (node (ref "R70") (pin "1") (pinfunction "1_1") (pintype "passive"))
      (node (ref "R85") (pin "1") (pinfunction "1_1") (pintype "passive"))
      (node (ref "U10") (pin "5") (pinfunction "FB_5") (pintype "bidirectional"))
    )
    (net (code "76") (name "Net-(U10-SS)") (class "Default")
      (node (ref "C52") (pin "1") (pinfunction "1_1") (pintype "passive"))
      (node (ref "U10") (pin "8") (pinfunction "SS_8") (pintype "bidirectional"))
    )
    (net (code "77") (name "Net-(U10-SW)") (class "Default")
      (node (ref "C49") (pin "2") (pinfunction "2_2") (pintype "passive"))
      (node (ref "L11") (pin "1") (pinfunction "1_1") (pintype "passive"))
      (node (ref "U10") (pin "3") (pinfunction "SW_3") (pintype "bidirectional"))
    )
    (net (code "78") (name "Net-(USB_HOST-5)") (class "Default")
      (node (ref "L6") (pin "2") (pinfunction "2_2") (pintype "passive"))
      (node (ref "USB_HOST") (pin "P$1") (pinfunction "5_P$1") (pintype "input"))
      (node (ref "USB_HOST") (pin "P$2") (pinfunction "6_P$2") (pintype "input"))
    )
    (net (code "79") (name "SYS_RESETN") (class "Default")
      (node (ref "AM3352-SOM-EVB-PLATFORM") (pin "4-28") (pinfunction "SYS_RESETN_4-28") (pintype "passive"))
      (node (ref "IC4") (pin "4") (pinfunction "~{RST}_4") (pintype "bidirectional"))
      (node (ref "TLV320AIC3107") (pin "31") (pinfunction "RESETN_31") (pintype "bidirectional"))
    )
    (net (code "80") (name "USB0_CE") (class "Default")
      (node (ref "AM3352-SOM-EVB-PLATFORM") (pin "3-14") (pinfunction "USB0_CE_3-14") (pintype "passive"))
      (node (ref "R2") (pin "2") (pinfunction "2_2") (pintype "passive"))
    )
    (net (code "81") (name "USB0_DM") (class "Default")
      (node (ref "AM3352-SOM-EVB-PLATFORM") (pin "3-15") (pinfunction "USB0_DM_3-15") (pintype "passive"))
      (node (ref "USB_OTG") (pin "D-") (pinfunction "D-_D-") (pintype "input"))
    )
    (net (code "82") (name "USB0_DP") (class "Default")
      (node (ref "AM3352-SOM-EVB-PLATFORM") (pin "3-13") (pinfunction "USB0_DP_3-13") (pintype "passive"))
      (node (ref "USB_OTG") (pin "D+") (pinfunction "D+_D+") (pintype "input"))
    )
    (net (code "83") (name "USB0_DRV") (class "Default")
      (node (ref "AM3352-SOM-EVB-PLATFORM") (pin "3-16") (pinfunction "USB0-DRV_3-16") (pintype "passive"))
      (node (ref "R2") (pin "1") (pinfunction "1_1") (pintype "passive"))
      (node (ref "R4") (pin "2") (pinfunction "2_2") (pintype "passive"))
      (node (ref "U1") (pin "4") (pinfunction "EN_4") (pintype "bidirectional"))
    )
    (net (code "84") (name "USB0_ID") (class "Default")
      (node (ref "AM3352-SOM-EVB-PLATFORM") (pin "3-12") (pinfunction "USB0-ID_3-12") (pintype "passive"))
      (node (ref "USB_OTG") (pin "ID") (pinfunction "ID_ID") (pintype "input"))
    )
    (net (code "85") (name "USB0_VBUS") (class "Default")
      (node (ref "AM3352-SOM-EVB-PLATFORM") (pin "3-11") (pinfunction "USB0-VBUS_3-11") (pintype "passive"))
      (node (ref "R1") (pin "1") (pinfunction "1_1") (pintype "passive"))
    )
    (net (code "86") (name "USB1_CE") (class "Default")
      (node (ref "AM3352-SOM-EVB-PLATFORM") (pin "3-8") (pinfunction "USB1_CE_3-8") (pintype "passive"))
      (node (ref "R23") (pin "2") (pinfunction "2_2") (pintype "passive"))
    )
    (net (code "87") (name "USB1_DM") (class "Default")
      (node (ref "AM3352-SOM-EVB-PLATFORM") (pin "3-9") (pinfunction "USB1_DM_3-9") (pintype "passive"))
      (node (ref "OOBDPICAN") (pin "2") (pinfunction "2_2") (pintype "passive"))
      (node (ref "USB_HOST") (pin "2") (pinfunction "2_2") (pintype "passive"))
    )
    (net (code "88") (name "USB1_DP") (class "Default")
      (node (ref "AM3352-SOM-EVB-PLATFORM") (pin "3-7") (pinfunction "USB1_DP_3-7") (pintype "passive"))
      (node (ref "OOBDPICAN") (pin "4") (pinfunction "4_4") (pintype "passive"))
      (node (ref "USB_HOST") (pin "3") (pinfunction "3_3") (pintype "passive"))
    )
    (net (code "89") (name "USB1_DRV") (class "Default")
      (node (ref "AM3352-SOM-EVB-PLATFORM") (pin "3-10") (pinfunction "USB1_DRV_3-10") (pintype "passive"))
      (node (ref "R21") (pin "2") (pinfunction "2_2") (pintype "passive"))
      (node (ref "R23") (pin "1") (pinfunction "1_1") (pintype "passive"))
      (node (ref "U3") (pin "4") (pinfunction "EN_4") (pintype "bidirectional"))
    )
    (net (code "90") (name "USB1_ID") (class "Default")
      (node (ref "AM3352-SOM-EVB-PLATFORM") (pin "3-6") (pinfunction "USB1_ID_3-6") (pintype "passive"))
      (node (ref "R24") (pin "2") (pinfunction "2_2") (pintype "passive"))
    )
    (net (code "91") (name "USB1_VBUS") (class "Default")
      (node (ref "AM3352-SOM-EVB-PLATFORM") (pin "3-5") (pinfunction "USB1-VBUS_3-5") (pintype "passive"))
      (node (ref "R22") (pin "1") (pinfunction "1_1") (pintype "passive"))
    )
    (net (code "92") (name "unconnected-(AM3352-SOM-EVB-PLATFORM-AIN4-Pad4-35)") (class "Default")
      (node (ref "AM3352-SOM-EVB-PLATFORM") (pin "4-35") (pinfunction "AIN4_4-35") (pintype "passive"))
    )
    (net (code "93") (name "unconnected-(AM3352-SOM-EVB-PLATFORM-AIN5-Pad4-37)") (class "Default")
      (node (ref "AM3352-SOM-EVB-PLATFORM") (pin "4-37") (pinfunction "AIN5_4-37") (pintype "passive"))
    )
    (net (code "94") (name "unconnected-(AM3352-SOM-EVB-PLATFORM-AIN6-Pad4-38)") (class "Default")
      (node (ref "AM3352-SOM-EVB-PLATFORM") (pin "4-38") (pinfunction "AIN6_4-38") (pintype "passive"))
    )
    (net (code "95") (name "unconnected-(AM3352-SOM-EVB-PLATFORM-AIN7-Pad4-36)") (class "Default")
      (node (ref "AM3352-SOM-EVB-PLATFORM") (pin "4-36") (pinfunction "AIN7_4-36") (pintype "passive"))
    )
    (net (code "96") (name "unconnected-(AM3352-SOM-EVB-PLATFORM-JTAG_TCK-Pad4-29)") (class "Default")
      (node (ref "AM3352-SOM-EVB-PLATFORM") (pin "4-29") (pinfunction "JTAG_TCK_4-29") (pintype "passive"))
    )
    (net (code "97") (name "unconnected-(AM3352-SOM-EVB-PLATFORM-JTAG_TDI-Pad4-31)") (class "Default")
      (node (ref "AM3352-SOM-EVB-PLATFORM") (pin "4-31") (pinfunction "JTAG_TDI_4-31") (pintype "passive"))
    )
    (net (code "98") (name "unconnected-(AM3352-SOM-EVB-PLATFORM-JTAG_TDO-Pad4-33)") (class "Default")
      (node (ref "AM3352-SOM-EVB-PLATFORM") (pin "4-33") (pinfunction "JTAG_TDO_4-33") (pintype "passive"))
    )
    (net (code "99") (name "unconnected-(AM3352-SOM-EVB-PLATFORM-JTAG_TMS-Pad4-32)") (class "Default")
      (node (ref "AM3352-SOM-EVB-PLATFORM") (pin "4-32") (pinfunction "JTAG_TMS_4-32") (pintype "passive"))
    )
    (net (code "100") (name "unconnected-(AM3352-SOM-EVB-PLATFORM-JTAG_TRST-Pad4-30)") (class "Default")
      (node (ref "AM3352-SOM-EVB-PLATFORM") (pin "4-30") (pinfunction "JTAG_TRST_4-30") (pintype "passive"))
    )
    (net (code "101") (name "unconnected-(AM3352-SOM-EVB-PLATFORM-MMC0-SDCD#{slash}EMU4-Pad3-17)") (class "Default")
      (node (ref "AM3352-SOM-EVB-PLATFORM") (pin "3-17") (pinfunction "MMC0-SDCD#/EMU4_3-17") (pintype "passive"))
    )
    (net (code "102") (name "unconnected-(AM3352-SOM-EVB-PLATFORM-NNMI-Pad3-22)") (class "Default")
      (node (ref "AM3352-SOM-EVB-PLATFORM") (pin "3-22") (pinfunction "NNMI_3-22") (pintype "passive"))
    )
    (net (code "103") (name "unconnected-(AM3352-SOM-EVB-PLATFORM-P0_0{slash}EMDIO-Pad3-38)") (class "Default")
      (node (ref "AM3352-SOM-EVB-PLATFORM") (pin "3-38") (pinfunction "P0_0/EMDIO_3-38") (pintype "passive"))
    )
    (net (code "104") (name "unconnected-(AM3352-SOM-EVB-PLATFORM-P0_1{slash}EMDC-Pad3-36)") (class "Default")
      (node (ref "AM3352-SOM-EVB-PLATFORM") (pin "3-36") (pinfunction "P0_1/EMDC_3-36") (pintype "passive"))
    )
    (net (code "105") (name "unconnected-(AM3352-SOM-EVB-PLATFORM-P0_2{slash}SPI0_SCLK-Pad4-11)") (class "Default")
      (node (ref "AM3352-SOM-EVB-PLATFORM") (pin "4-11") (pinfunction "P0_2/SPI0_SCLK_4-11") (pintype "passive"))
    )
    (net (code "106") (name "unconnected-(AM3352-SOM-EVB-PLATFORM-P0_3{slash}SPI0_D0(MISO)-Pad4-9)") (class "Default")
      (node (ref "AM3352-SOM-EVB-PLATFORM") (pin "4-9") (pinfunction "P0_3/SPI0_D0(MISO)_4-9") (pintype "passive"))
    )
    (net (code "107") (name "unconnected-(AM3352-SOM-EVB-PLATFORM-P0_4{slash}SPI0_D1(MOSI)-Pad4-10)") (class "Default")
      (node (ref "AM3352-SOM-EVB-PLATFORM") (pin "4-10") (pinfunction "P0_4/SPI0_D1(MOSI)_4-10") (pintype "passive"))
    )
    (net (code "108") (name "unconnected-(AM3352-SOM-EVB-PLATFORM-P0_5{slash}SPI0_CS0-Pad4-12)") (class "Default")
      (node (ref "AM3352-SOM-EVB-PLATFORM") (pin "4-12") (pinfunction "P0_5/SPI0_CS0_4-12") (pintype "passive"))
    )
    (net (code "109") (name "unconnected-(AM3352-SOM-EVB-PLATFORM-P0_7{slash}PWM0_OUT-Pad4-27)") (class "Default")
      (node (ref "AM3352-SOM-EVB-PLATFORM") (pin "4-27") (pinfunction "P0_7/PWM0_OUT_4-27") (pintype "passive"))
    )
    (net (code "110") (name "unconnected-(AM3352-SOM-EVB-PLATFORM-P0_14{slash}UART1_RXD-Pad4-6)") (class "Default")
      (node (ref "AM3352-SOM-EVB-PLATFORM") (pin "4-6") (pinfunction "P0_14/UART1_RXD_4-6") (pintype "passive"))
    )
    (net (code "111") (name "unconnected-(AM3352-SOM-EVB-PLATFORM-P0_15{slash}UART1_TXD-Pad4-5)") (class "Default")
      (node (ref "AM3352-SOM-EVB-PLATFORM") (pin "4-5") (pinfunction "P0_15/UART1_TXD_4-5") (pintype "passive"))
    )
    (net (code "112") (name "unconnected-(AM3352-SOM-EVB-PLATFORM-P0_16{slash}ETXD3-Pad3-29)") (class "Default")
      (node (ref "AM3352-SOM-EVB-PLATFORM") (pin "3-29") (pinfunction "P0_16/ETXD3_3-29") (pintype "passive"))
    )
    (net (code "113") (name "unconnected-(AM3352-SOM-EVB-PLATFORM-P0_17{slash}ETXD2-Pad3-27)") (class "Default")
      (node (ref "AM3352-SOM-EVB-PLATFORM") (pin "3-27") (pinfunction "P0_17/ETXD2_3-27") (pintype "passive"))
    )
    (net (code "114") (name "unconnected-(AM3352-SOM-EVB-PLATFORM-P0_20{slash}EMU3-Pad4-22)") (class "Default")
      (node (ref "AM3352-SOM-EVB-PLATFORM") (pin "4-22") (pinfunction "P0_20/EMU3_4-22") (pintype "passive"))
    )
    (net (code "115") (name "unconnected-(AM3352-SOM-EVB-PLATFORM-P0_21{slash}ETXD1-Pad3-25)") (class "Default")
      (node (ref "AM3352-SOM-EVB-PLATFORM") (pin "3-25") (pinfunction "P0_21/ETXD1_3-25") (pintype "passive"))
    )
    (net (code "116") (name "unconnected-(AM3352-SOM-EVB-PLATFORM-P0_28{slash}ETXD0-Pad3-23)") (class "Default")
      (node (ref "AM3352-SOM-EVB-PLATFORM") (pin "3-23") (pinfunction "P0_28/ETXD0_3-23") (pintype "passive"))
    )
    (net (code "117") (name "unconnected-(AM3352-SOM-EVB-PLATFORM-P0_29{slash}EPHY-RST#{slash}RFCLK-Pad3-40)") (class "Default")
      (node (ref "AM3352-SOM-EVB-PLATFORM") (pin "3-40") (pinfunction "P0_29/EPHY-RST#/RFCLK_3-40") (pintype "passive"))
    )
    (net (code "118") (name "unconnected-(AM3352-SOM-EVB-PLATFORM-P2_18{slash}ERXD3-Pad3-30)") (class "Default")
      (node (ref "AM3352-SOM-EVB-PLATFORM") (pin "3-30") (pinfunction "P2_18/ERXD3_3-30") (pintype "passive"))
    )
    (net (code "119") (name "unconnected-(AM3352-SOM-EVB-PLATFORM-P2_19{slash}ERXD2-Pad3-28)") (class "Default")
      (node (ref "AM3352-SOM-EVB-PLATFORM") (pin "3-28") (pinfunction "P2_19/ERXD2_3-28") (pintype "passive"))
    )
    (net (code "120") (name "unconnected-(AM3352-SOM-EVB-PLATFORM-P2_20{slash}ERXD1-Pad3-26)") (class "Default")
      (node (ref "AM3352-SOM-EVB-PLATFORM") (pin "3-26") (pinfunction "P2_20/ERXD1_3-26") (pintype "passive"))
    )
    (net (code "121") (name "unconnected-(AM3352-SOM-EVB-PLATFORM-P2_21{slash}ERXD0-Pad3-24)") (class "Default")
      (node (ref "AM3352-SOM-EVB-PLATFORM") (pin "3-24") (pinfunction "P2_21/ERXD0_3-24") (pintype "passive"))
    )
    (net (code "122") (name "unconnected-(AM3352-SOM-EVB-PLATFORM-P3_0{slash}ECOL-Pad3-37)") (class "Default")
      (node (ref "AM3352-SOM-EVB-PLATFORM") (pin "3-37") (pinfunction "P3_0/ECOL_3-37") (pintype "passive"))
    )
    (net (code "123") (name "unconnected-(AM3352-SOM-EVB-PLATFORM-P3_1{slash}ECRS-Pad3-39)") (class "Default")
      (node (ref "AM3352-SOM-EVB-PLATFORM") (pin "3-39") (pinfunction "P3_1/ECRS_3-39") (pintype "passive"))
    )
    (net (code "124") (name "unconnected-(AM3352-SOM-EVB-PLATFORM-P3_2{slash}ERXERR-Pad3-35)") (class "Default")
      (node (ref "AM3352-SOM-EVB-PLATFORM") (pin "3-35") (pinfunction "P3_2/ERXERR_3-35") (pintype "passive"))
    )
    (net (code "125") (name "unconnected-(AM3352-SOM-EVB-PLATFORM-P3_3{slash}ETXEN-Pad3-31)") (class "Default")
      (node (ref "AM3352-SOM-EVB-PLATFORM") (pin "3-31") (pinfunction "P3_3/ETXEN_3-31") (pintype "passive"))
    )
    (net (code "126") (name "unconnected-(AM3352-SOM-EVB-PLATFORM-P3_4{slash}ERXDV-Pad3-32)") (class "Default")
      (node (ref "AM3352-SOM-EVB-PLATFORM") (pin "3-32") (pinfunction "P3_4/ERXDV_3-32") (pintype "passive"))
    )
    (net (code "127") (name "unconnected-(AM3352-SOM-EVB-PLATFORM-P3_9{slash}ETXCK-Pad3-33)") (class "Default")
      (node (ref "AM3352-SOM-EVB-PLATFORM") (pin "3-33") (pinfunction "P3_9/ETXCK_3-33") (pintype "passive"))
    )
    (net (code "128") (name "unconnected-(AM3352-SOM-EVB-PLATFORM-P3_10{slash}ERXCK-Pad3-34)") (class "Default")
      (node (ref "AM3352-SOM-EVB-PLATFORM") (pin "3-34") (pinfunction "P3_10/ERXCK_3-34") (pintype "passive"))
    )
    (net (code "129") (name "unconnected-(AM3352-SOM-EVB-PLATFORM-PMIC_POWER_EN-Pad3-18)") (class "Default")
      (node (ref "AM3352-SOM-EVB-PLATFORM") (pin "3-18") (pinfunction "PMIC_POWER_EN_3-18") (pintype "passive"))
    )
    (net (code "130") (name "unconnected-(AM3352-SOM-EVB-PLATFORM-PWRONRSTN-Pad3-19)") (class "Default")
      (node (ref "AM3352-SOM-EVB-PLATFORM") (pin "3-19") (pinfunction "PWRONRSTN_3-19") (pintype "passive"))
    )
    (net (code "131") (name "unconnected-(AM3352-SOM-EVB-PLATFORM-SYS_RESETN-Pad3-21)") (class "Default")
      (node (ref "AM3352-SOM-EVB-PLATFORM") (pin "3-21") (pinfunction "SYS_RESETN_3-21") (pintype "passive"))
    )
    (net (code "132") (name "unconnected-(AM3352-SOM-EVB-PLATFORM-VDDA_ADC-Pad4-39)") (class "Default")
      (node (ref "AM3352-SOM-EVB-PLATFORM") (pin "4-39") (pinfunction "VDDA_ADC_4-39") (pintype "passive"))
    )
    (net (code "133") (name "unconnected-(AM3352-SOM-EVB-PLATFORM-VREFP-Pad4-34)") (class "Default")
      (node (ref "AM3352-SOM-EVB-PLATFORM") (pin "4-34") (pinfunction "VREFP_4-34") (pintype "passive"))
    )
    (net (code "134") (name "unconnected-(IC1-NC-Pad2)") (class "Default")
      (node (ref "IC1") (pin "2") (pinfunction "NC_2") (pintype "no_connect"))
    )
    (net (code "135") (name "unconnected-(IC1-V_REF-Pad14)") (class "Default")
      (node (ref "IC1") (pin "14") (pinfunction "V_REF_14") (pintype "output"))
    )
    (net (code "136") (name "unconnected-(IC2-NC-Pad2)") (class "Default")
      (node (ref "IC2") (pin "2") (pinfunction "NC_2") (pintype "no_connect"))
    )
    (net (code "137") (name "unconnected-(IC2-V_REF-Pad14)") (class "Default")
      (node (ref "IC2") (pin "14") (pinfunction "V_REF_14") (pintype "output"))
    )
    (net (code "138") (name "unconnected-(IC4-32KHZ-Pad1)") (class "Default")
      (node (ref "IC4") (pin "1") (pinfunction "32KHZ_1") (pintype "bidirectional"))
    )
    (net (code "139") (name "unconnected-(OOBD2-CONNECTOR-Pad4)") (class "Default")
      (node (ref "OOBD2-CONNECTOR") (pin "4") (pinfunction "4_4") (pintype "passive"))
    )
    (net (code "140") (name "unconnected-(OOBD2-CONNECTOR-Pad5)") (class "Default")
      (node (ref "OOBD2-CONNECTOR") (pin "5") (pinfunction "5_5") (pintype "passive"))
    )
    (net (code "141") (name "unconnected-(OOBD2-CONNECTOR-Pad8)") (class "Default")
      (node (ref "OOBD2-CONNECTOR") (pin "8") (pinfunction "8_8") (pintype "passive"))
    )
    (net (code "142") (name "unconnected-(OOBD2-CONNECTOR-Pad9)") (class "Default")
      (node (ref "OOBD2-CONNECTOR") (pin "9") (pinfunction "9_9") (pintype "passive"))
    )
    (net (code "143") (name "unconnected-(OOBDPICAN-Pad3)") (class "Default")
      (node (ref "OOBDPICAN") (pin "3") (pinfunction "3_3") (pintype "passive"))
    )
    (net (code "144") (name "unconnected-(OOBDPICAN-Pad6)") (class "Default")
      (node (ref "OOBDPICAN") (pin "6") (pinfunction "6_6") (pintype "passive"))
    )
    (net (code "145") (name "unconnected-(TLV320AIC3107-GPIO1-Pad32)") (class "Default")
      (node (ref "TLV320AIC3107") (pin "32") (pinfunction "GPIO1_32") (pintype "bidirectional"))
    )
    (net (code "146") (name "unconnected-(TLV320AIC3107-HPCOM-Pad15)") (class "Default")
      (node (ref "TLV320AIC3107") (pin "15") (pinfunction "HPCOM_15") (pintype "bidirectional"))
    )
    (net (code "147") (name "unconnected-(TLV320AIC3107-HPLOUT-Pad14)") (class "Default")
      (node (ref "TLV320AIC3107") (pin "14") (pinfunction "HPLOUT_14") (pintype "bidirectional"))
    )
    (net (code "148") (name "unconnected-(TLV320AIC3107-HPROUT-Pad17)") (class "Default")
      (node (ref "TLV320AIC3107") (pin "17") (pinfunction "HPROUT_17") (pintype "bidirectional"))
    )
    (net (code "149") (name "unconnected-(TLV320AIC3107-LEFT_LOP-Pad19)") (class "Default")
      (node (ref "TLV320AIC3107") (pin "19") (pinfunction "LEFT_LOP_19") (pintype "bidirectional"))
    )
    (net (code "150") (name "unconnected-(TLV320AIC3107-LINE1LP-Pad4)") (class "Default")
      (node (ref "TLV320AIC3107") (pin "4") (pinfunction "LINE1LP_4") (pintype "bidirectional"))
    )
    (net (code "151") (name "unconnected-(TLV320AIC3107-LINE1RP-Pad5)") (class "Default")
      (node (ref "TLV320AIC3107") (pin "5") (pinfunction "LINE1RP_5") (pintype "bidirectional"))
    )
    (net (code "152") (name "unconnected-(TLV320AIC3107-LINE2LP-Pad7)") (class "Default")
      (node (ref "TLV320AIC3107") (pin "7") (pinfunction "LINE2LP_7") (pintype "bidirectional"))
    )
    (net (code "153") (name "unconnected-(TLV320AIC3107-LINE2RP{slash}LINE2LM-Pad8)") (class "Default")
      (node (ref "TLV320AIC3107") (pin "8") (pinfunction "LINE2RP/LINE2LM_8") (pintype "bidirectional"))
    )
    (net (code "154") (name "unconnected-(TLV320AIC3107-MIC3L{slash}LINE1RM-Pad6)") (class "Default")
      (node (ref "TLV320AIC3107") (pin "6") (pinfunction "MIC3L/LINE1RM_6") (pintype "bidirectional"))
    )
    (net (code "155") (name "unconnected-(TLV320AIC3107-MIC3R{slash}LINE2RM-Pad9)") (class "Default")
      (node (ref "TLV320AIC3107") (pin "9") (pinfunction "MIC3R/LINE2RM_9") (pintype "bidirectional"))
    )
    (net (code "156") (name "unconnected-(TLV320AIC3107-MICBIAS-Pad10)") (class "Default")
      (node (ref "TLV320AIC3107") (pin "10") (pinfunction "MICBIAS_10") (pintype "bidirectional"))
    )
    (net (code "157") (name "unconnected-(TLV320AIC3107-MICDET{slash}LINE1LM-Pad3)") (class "Default")
      (node (ref "TLV320AIC3107") (pin "3") (pinfunction "MICDET/LINE1LM_3") (pintype "bidirectional"))
    )
    (net (code "158") (name "unconnected-(TLV320AIC3107-RIGHT_LOP-Pad20)") (class "Default")
      (node (ref "TLV320AIC3107") (pin "20") (pinfunction "RIGHT_LOP_20") (pintype "bidirectional"))
    )
    (net (code "159") (name "unconnected-(TLV320AIC3107-SWINM-Pad27)") (class "Default")
      (node (ref "TLV320AIC3107") (pin "27") (pinfunction "SWINM_27") (pintype "bidirectional"))
    )
    (net (code "160") (name "unconnected-(TLV320AIC3107-SWINP-Pad30)") (class "Default")
      (node (ref "TLV320AIC3107") (pin "30") (pinfunction "SWINP_30") (pintype "bidirectional"))
    )
    (net (code "161") (name "unconnected-(U2-VREF-Pad5)") (class "Default")
      (node (ref "U2") (pin "5") (pinfunction "VREF_5") (pintype "output"))
    )
    (net (code "162") (name "unconnected-(U6-VREF-Pad5)") (class "Default")
      (node (ref "U6") (pin "5") (pinfunction "VREF_5") (pintype "output"))
    )
  )
)
